# host.net
KiCad netlist of a schematic drawn in EAGLE
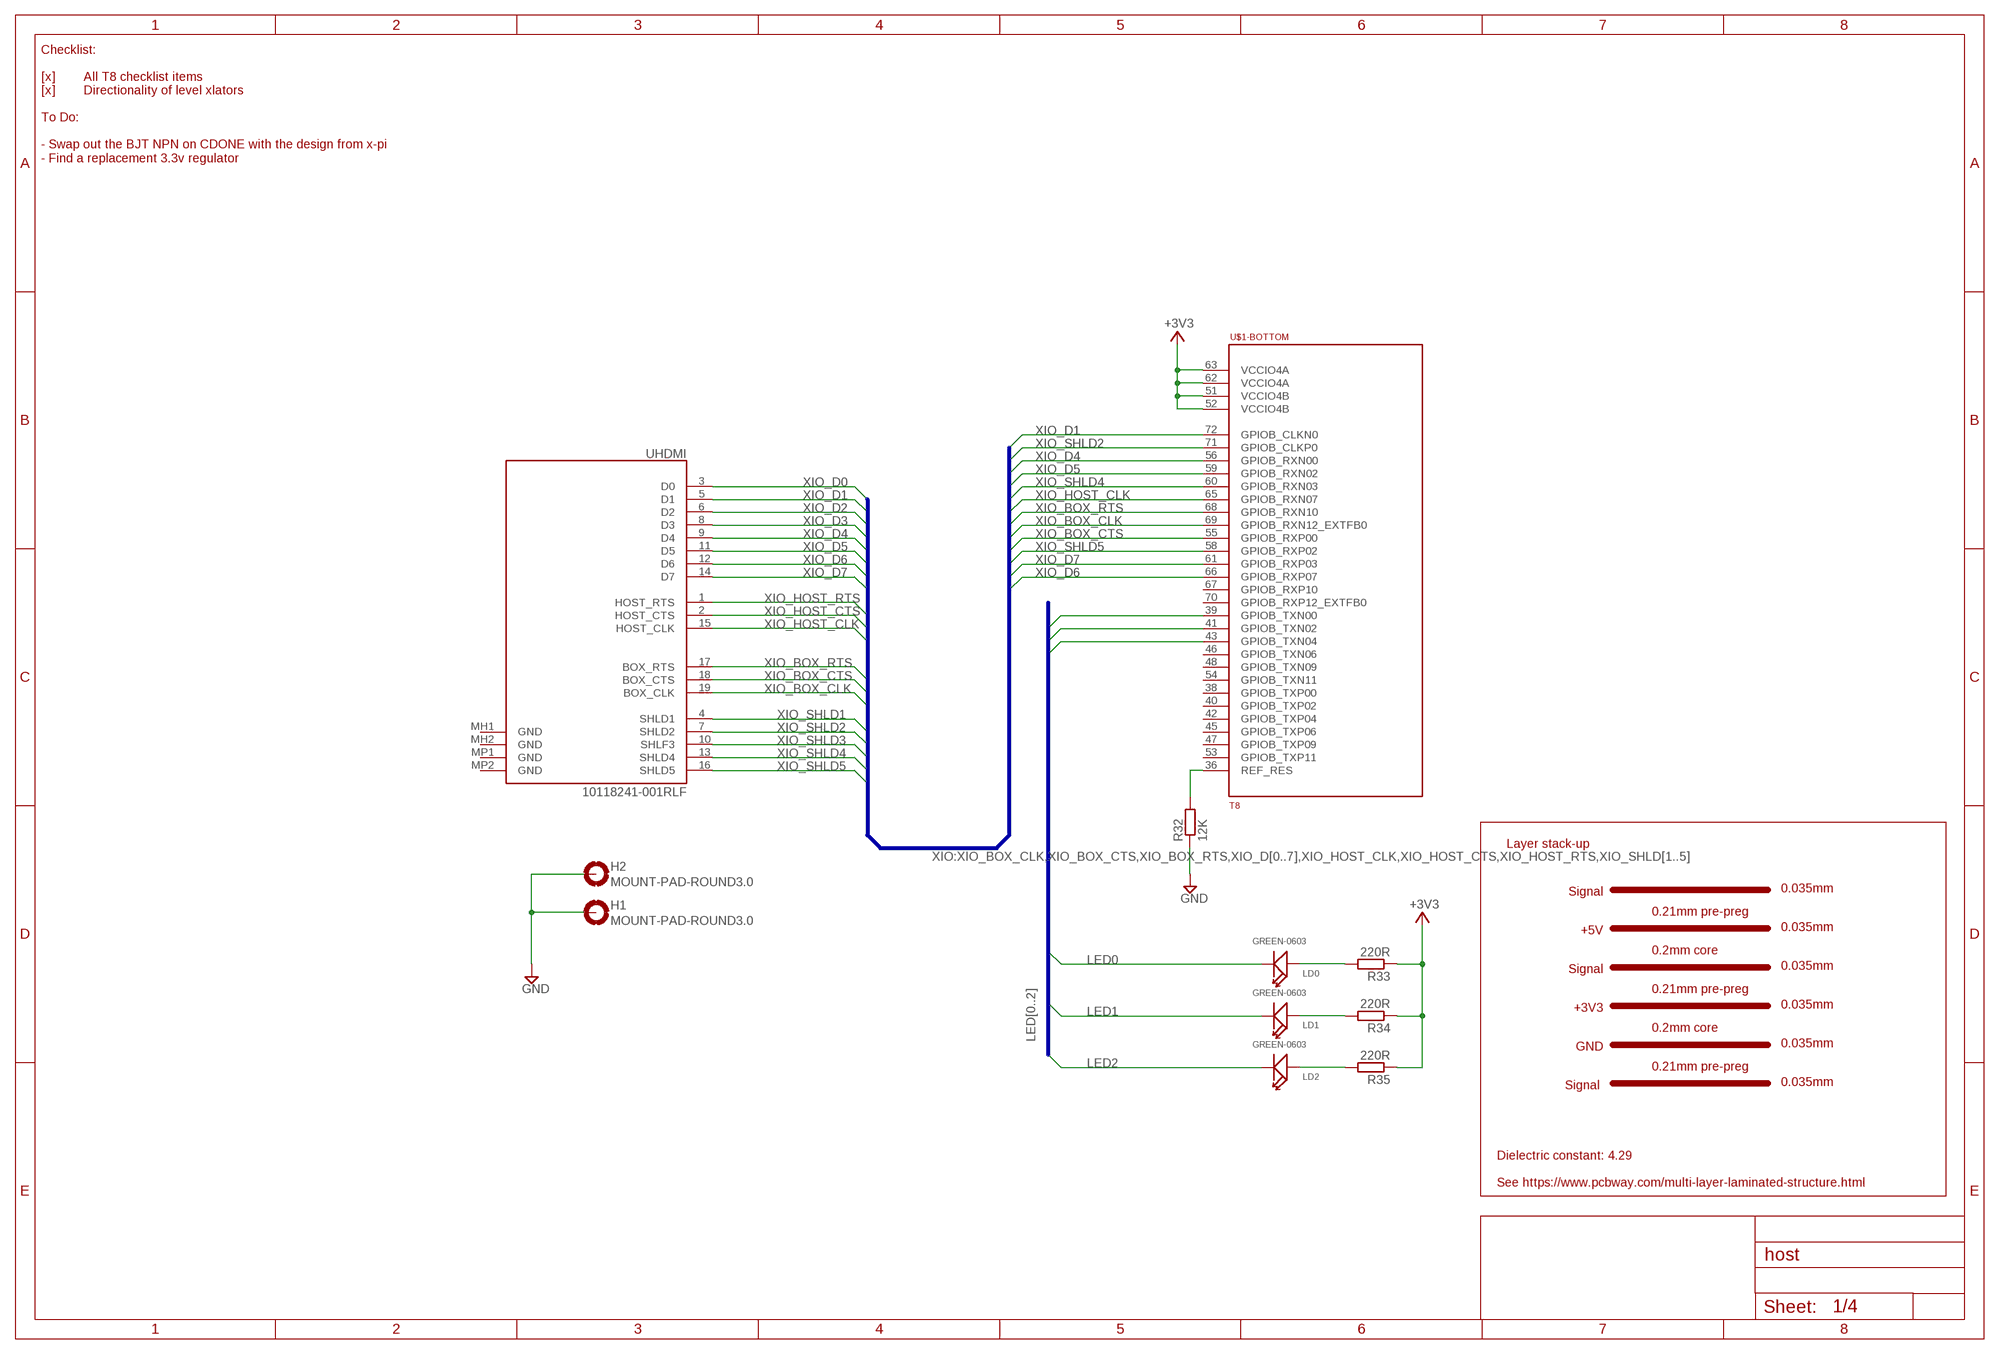
[diagram p0: schematic, sheet 1]
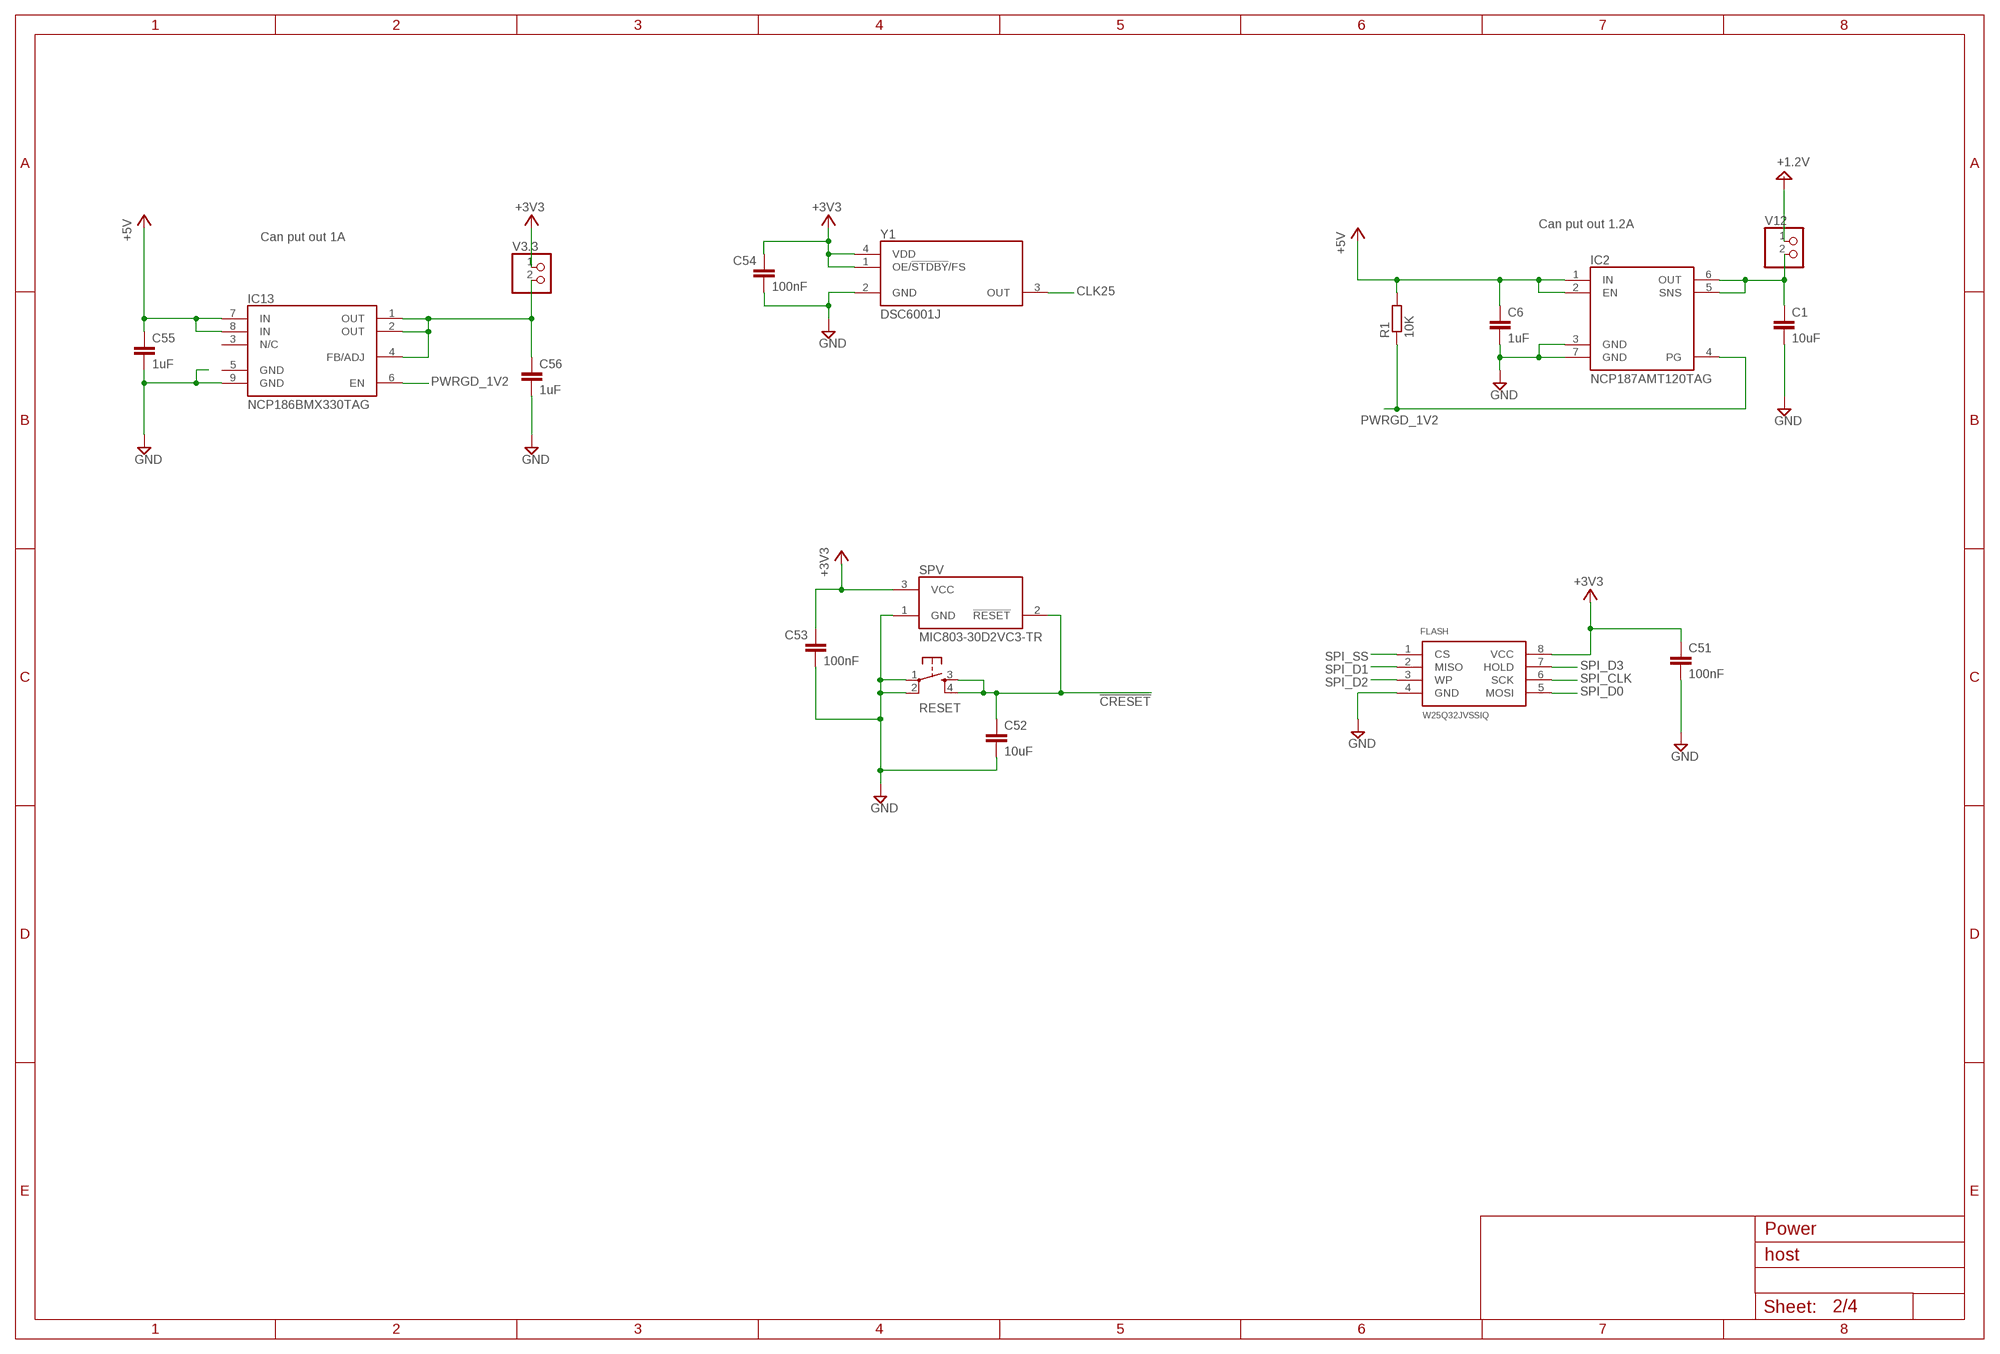
[diagram p1: schematic, sheet 2]
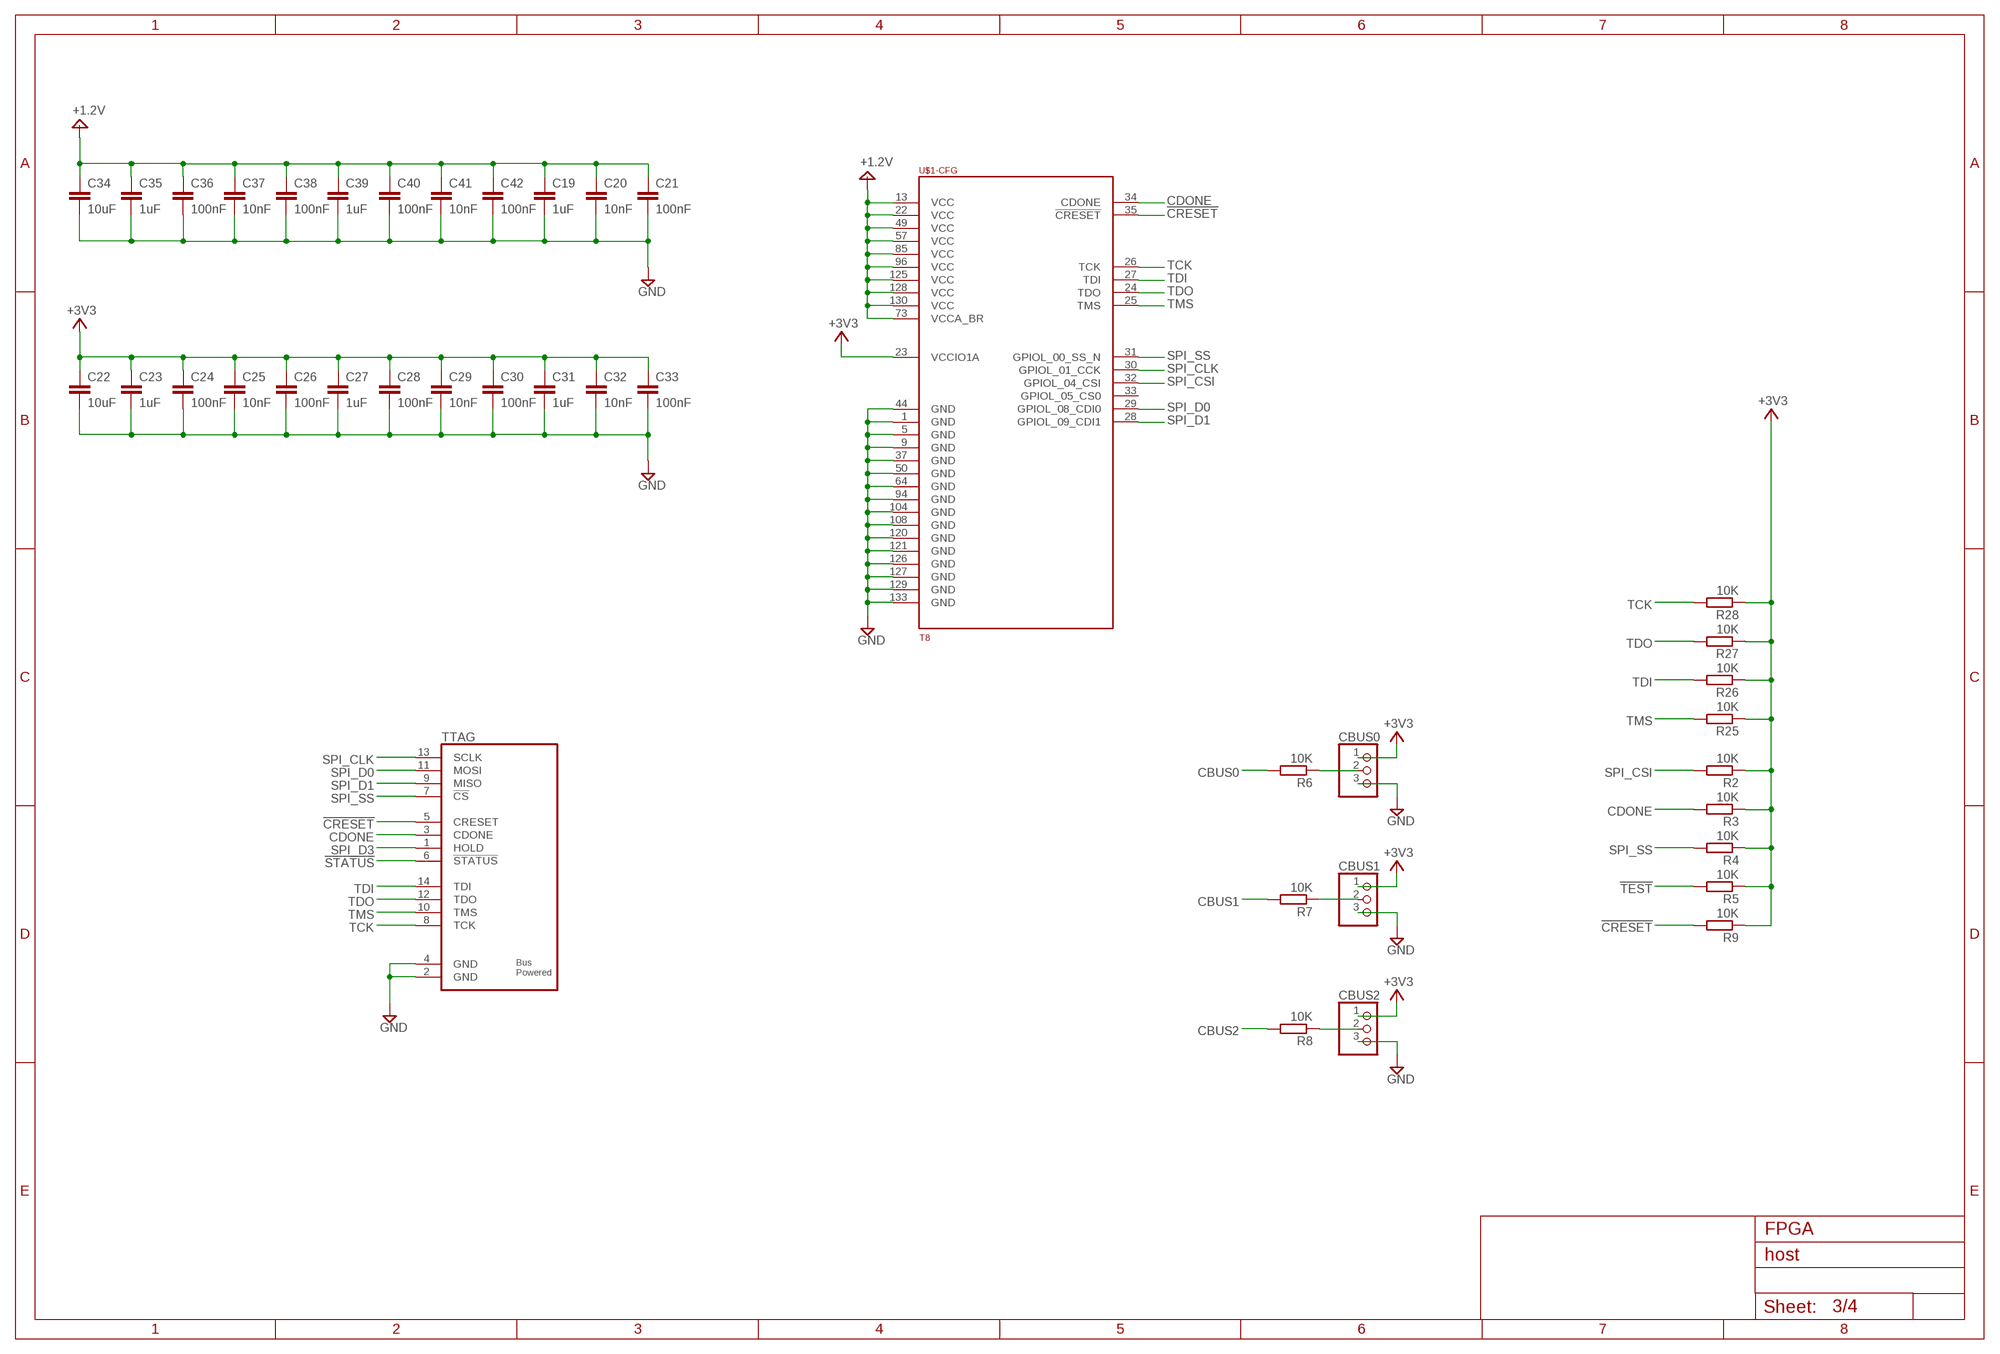
[diagram p2: schematic, sheet 3]
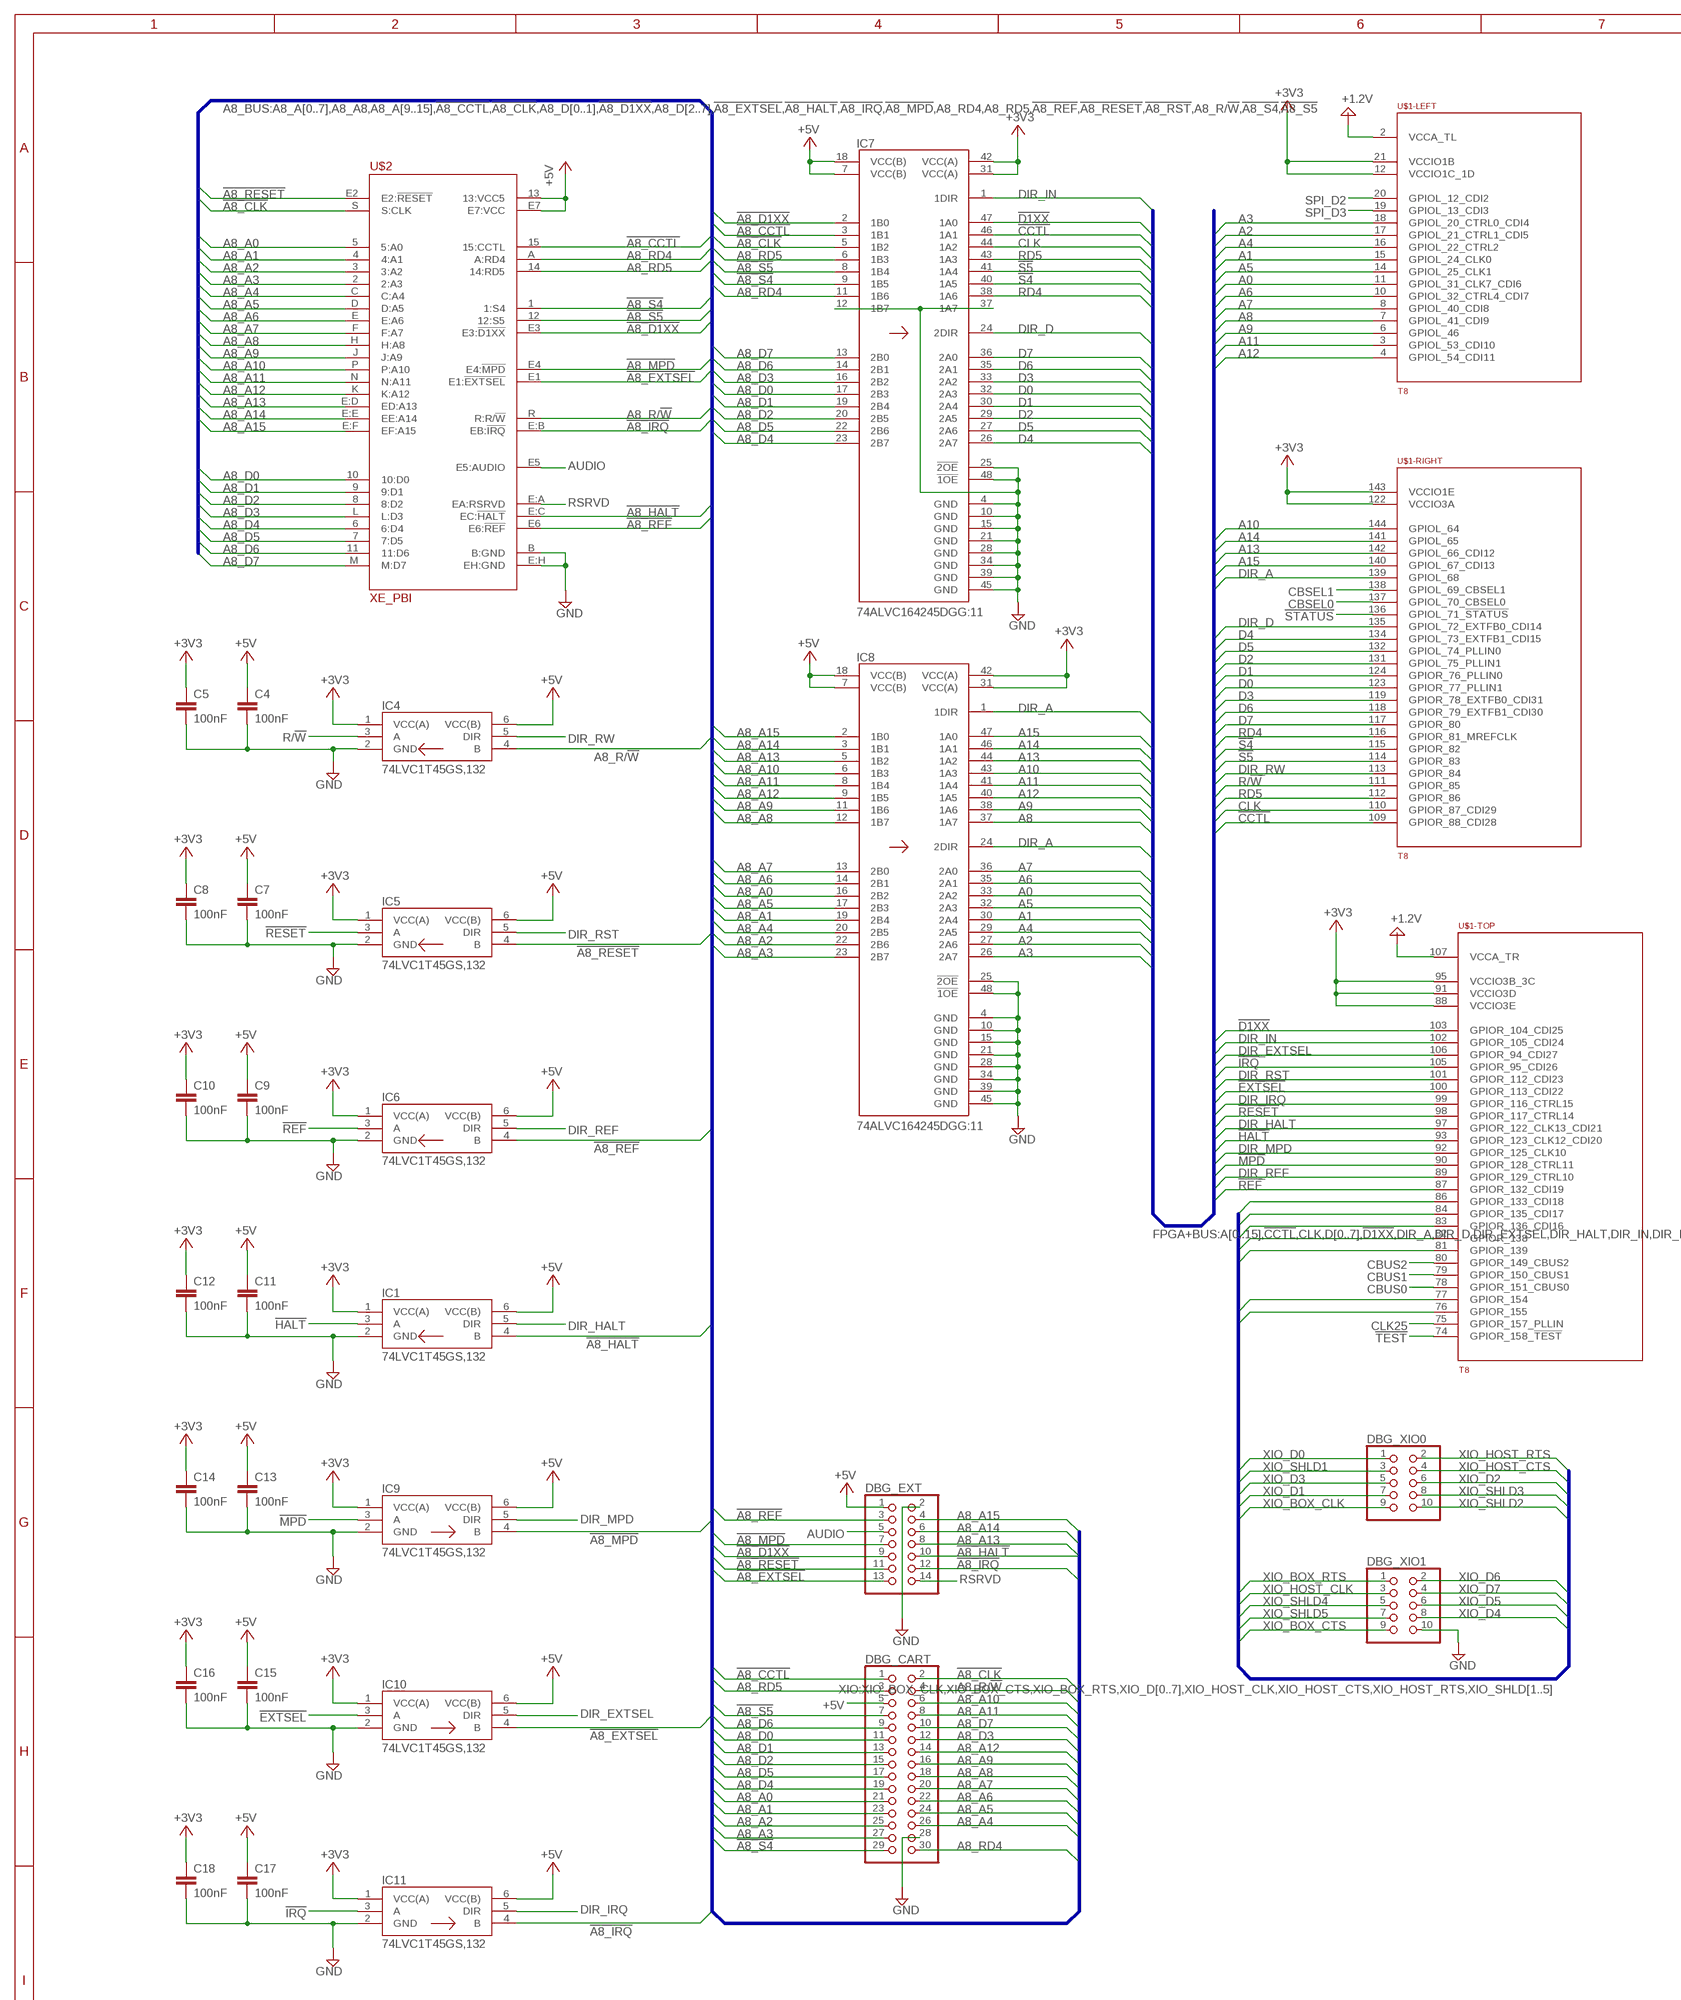
[diagram p3: schematic, sheet 4, part 1 of 2]
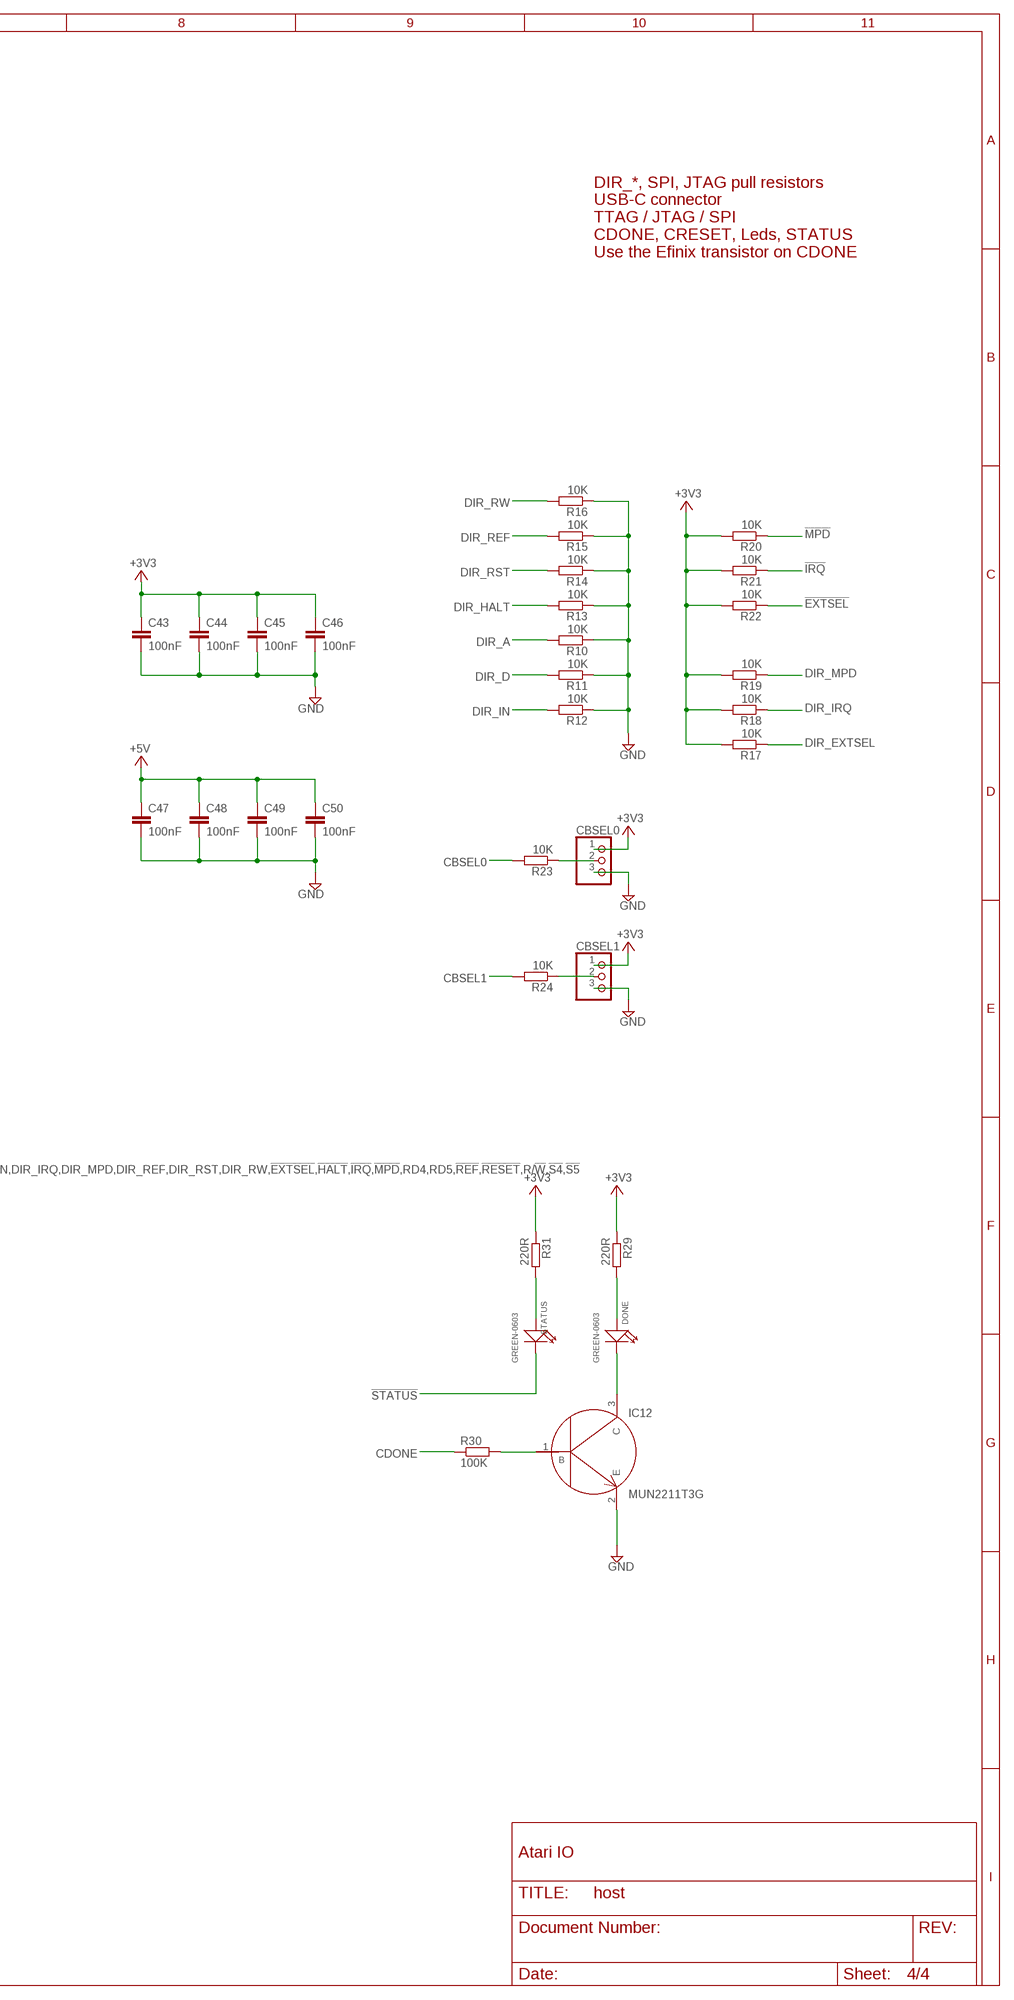
[diagram p4: schematic, sheet 4, part 2 of 2]

(export (version "E")
  (design (tool "Eeschema 10.0.6"))
  (components
    (comp (ref "H1")
      (value "MOUNT-PAD-ROUND3.0")
      (footprint "eagle-import:3,0-PAD")
      (libsource (lib "eagle-import") (part "MOUNT-PAD-ROUND3.0"))
    )
    (comp (ref "H2")
      (value "MOUNT-PAD-ROUND3.0")
      (footprint "eagle-import:3,0-PAD")
      (libsource (lib "eagle-import") (part "MOUNT-PAD-ROUND3.0"))
    )
    (comp (ref "LD0")
      (value "GREEN-0603")
      (footprint "eagle-import:LED-0603")
      (fields (field (name "MPN") "19-217-G7C-AN1P2-3T"))
      (libsource (lib "eagle-import") (part "SMD-LED-CLEAR-GREEN(0603)"))
    )
    (comp (ref "LD1")
      (value "GREEN-0603")
      (footprint "eagle-import:LED-0603")
      (fields (field (name "MPN") "19-217-G7C-AN1P2-3T"))
      (libsource (lib "eagle-import") (part "SMD-LED-CLEAR-GREEN(0603)"))
    )
    (comp (ref "LD2")
      (value "GREEN-0603")
      (footprint "eagle-import:LED-0603")
      (fields (field (name "MPN") "19-217-G7C-AN1P2-3T"))
      (libsource (lib "eagle-import") (part "SMD-LED-CLEAR-GREEN(0603)"))
    )
    (comp (ref "R32")
      (value "12K")
      (footprint "eagle-import:R0201")
      (libsource (lib "eagle-import") (part "R-EU_R0201"))
    )
    (comp (ref "R33")
      (value "220R")
      (footprint "eagle-import:R0201")
      (libsource (lib "eagle-import") (part "R-EU_R0201"))
    )
    (comp (ref "R34")
      (value "220R")
      (footprint "eagle-import:R0201")
      (libsource (lib "eagle-import") (part "R-EU_R0201"))
    )
    (comp (ref "R35")
      (value "220R")
      (footprint "eagle-import:R0201")
      (libsource (lib "eagle-import") (part "R-EU_R0201"))
    )
    (comp (ref "U$1")
      (value "T8")
      (footprint "eagle-import:TQFP144")
      (fields (field (name "USE") "T8Q144I4"))
      (libsource (lib "eagle-import") (part "T8"))
    )
    (comp (ref "UHDMI")
      (value "10118241-001RLF")
      (footprint "eagle-import:10118241001RLF")
      (fields (field (name "MOUSER_PART_NUMBER") "649-10118241-001RLF"))
      (libsource (lib "eagle-import") (part "10118241-001RLF"))
    )
    (comp (ref "C19")
      (value "1uF")
      (footprint "eagle-import:C0201")
      (libsource (lib "eagle-import") (part "C-EUC0201"))
    )
    (comp (ref "C20")
      (value "10nF")
      (footprint "eagle-import:C0201")
      (libsource (lib "eagle-import") (part "C-EUC0201"))
    )
    (comp (ref "C21")
      (value "100nF")
      (footprint "eagle-import:C0201")
      (libsource (lib "eagle-import") (part "C-EUC0201"))
    )
    (comp (ref "C22")
      (value "10uF")
      (footprint "eagle-import:C0402K")
      (libsource (lib "eagle-import") (part "C-EUC0402K"))
    )
    (comp (ref "C23")
      (value "1uF")
      (footprint "eagle-import:C0201")
      (libsource (lib "eagle-import") (part "C-EUC0201"))
    )
    (comp (ref "C24")
      (value "100nF")
      (footprint "eagle-import:C0201")
      (libsource (lib "eagle-import") (part "C-EUC0201"))
    )
    (comp (ref "C25")
      (value "10nF")
      (footprint "eagle-import:C0201")
      (libsource (lib "eagle-import") (part "C-EUC0201"))
    )
    (comp (ref "C26")
      (value "100nF")
      (footprint "eagle-import:C0201")
      (libsource (lib "eagle-import") (part "C-EUC0201"))
    )
    (comp (ref "C27")
      (value "1uF")
      (footprint "eagle-import:C0201")
      (libsource (lib "eagle-import") (part "C-EUC0201"))
    )
    (comp (ref "C28")
      (value "100nF")
      (footprint "eagle-import:C0201")
      (libsource (lib "eagle-import") (part "C-EUC0201"))
    )
    (comp (ref "C29")
      (value "10nF")
      (footprint "eagle-import:C0201")
      (libsource (lib "eagle-import") (part "C-EUC0201"))
    )
    (comp (ref "C30")
      (value "100nF")
      (footprint "eagle-import:C0201")
      (libsource (lib "eagle-import") (part "C-EUC0201"))
    )
    (comp (ref "C31")
      (value "1uF")
      (footprint "eagle-import:C0201")
      (libsource (lib "eagle-import") (part "C-EUC0201"))
    )
    (comp (ref "C32")
      (value "10nF")
      (footprint "eagle-import:C0201")
      (libsource (lib "eagle-import") (part "C-EUC0201"))
    )
    (comp (ref "C33")
      (value "100nF")
      (footprint "eagle-import:C0201")
      (libsource (lib "eagle-import") (part "C-EUC0201"))
    )
    (comp (ref "C34")
      (value "10uF")
      (footprint "eagle-import:C0402K")
      (libsource (lib "eagle-import") (part "C-EUC0402K"))
    )
    (comp (ref "C35")
      (value "1uF")
      (footprint "eagle-import:C0201")
      (libsource (lib "eagle-import") (part "C-EUC0201"))
    )
    (comp (ref "C36")
      (value "100nF")
      (footprint "eagle-import:C0201")
      (libsource (lib "eagle-import") (part "C-EUC0201"))
    )
    (comp (ref "C37")
      (value "10nF")
      (footprint "eagle-import:C0201")
      (libsource (lib "eagle-import") (part "C-EUC0201"))
    )
    (comp (ref "C38")
      (value "100nF")
      (footprint "eagle-import:C0201")
      (libsource (lib "eagle-import") (part "C-EUC0201"))
    )
    (comp (ref "C39")
      (value "1uF")
      (footprint "eagle-import:C0201")
      (libsource (lib "eagle-import") (part "C-EUC0201"))
    )
    (comp (ref "C40")
      (value "100nF")
      (footprint "eagle-import:C0201")
      (libsource (lib "eagle-import") (part "C-EUC0201"))
    )
    (comp (ref "C41")
      (value "10nF")
      (footprint "eagle-import:C0201")
      (libsource (lib "eagle-import") (part "C-EUC0201"))
    )
    (comp (ref "C42")
      (value "100nF")
      (footprint "eagle-import:C0201")
      (libsource (lib "eagle-import") (part "C-EUC0201"))
    )
    (comp (ref "CBUS0")
      (value "PINHD-1X3")
      (footprint "eagle-import:1X03")
      (libsource (lib "eagle-import") (part "PINHD-1X3"))
    )
    (comp (ref "CBUS1")
      (value "PINHD-1X3")
      (footprint "eagle-import:1X03")
      (libsource (lib "eagle-import") (part "PINHD-1X3"))
    )
    (comp (ref "CBUS2")
      (value "PINHD-1X3")
      (footprint "eagle-import:1X03")
      (libsource (lib "eagle-import") (part "PINHD-1X3"))
    )
    (comp (ref "R2")
      (value "10K")
      (footprint "eagle-import:R0201")
      (libsource (lib "eagle-import") (part "R-EU_R0201"))
    )
    (comp (ref "R3")
      (value "10K")
      (footprint "eagle-import:R0201")
      (libsource (lib "eagle-import") (part "R-EU_R0201"))
    )
    (comp (ref "R4")
      (value "10K")
      (footprint "eagle-import:R0201")
      (libsource (lib "eagle-import") (part "R-EU_R0201"))
    )
    (comp (ref "R5")
      (value "10K")
      (footprint "eagle-import:R0201")
      (libsource (lib "eagle-import") (part "R-EU_R0201"))
    )
    (comp (ref "R6")
      (value "10K")
      (footprint "eagle-import:R0201")
      (libsource (lib "eagle-import") (part "R-EU_R0201"))
    )
    (comp (ref "R7")
      (value "10K")
      (footprint "eagle-import:R0201")
      (libsource (lib "eagle-import") (part "R-EU_R0201"))
    )
    (comp (ref "R8")
      (value "10K")
      (footprint "eagle-import:R0201")
      (libsource (lib "eagle-import") (part "R-EU_R0201"))
    )
    (comp (ref "R9")
      (value "10K")
      (footprint "eagle-import:R0201")
      (libsource (lib "eagle-import") (part "R-EU_R0201"))
    )
    (comp (ref "R25")
      (value "10K")
      (footprint "eagle-import:R0201")
      (libsource (lib "eagle-import") (part "R-EU_R0201"))
    )
    (comp (ref "R26")
      (value "10K")
      (footprint "eagle-import:R0201")
      (libsource (lib "eagle-import") (part "R-EU_R0201"))
    )
    (comp (ref "R27")
      (value "10K")
      (footprint "eagle-import:R0201")
      (libsource (lib "eagle-import") (part "R-EU_R0201"))
    )
    (comp (ref "R28")
      (value "10K")
      (footprint "eagle-import:R0201")
      (libsource (lib "eagle-import") (part "R-EU_R0201"))
    )
    (comp (ref "TTAG")
      (value "TTAG_M_2.00")
      (footprint "eagle-import:2X07M")
      (libsource (lib "eagle-import") (part "TTAG_M_2.00"))
    )
    (comp (ref "C1")
      (value "10uF")
      (footprint "eagle-import:C0402K")
      (libsource (lib "eagle-import") (part "C-EUC0402K"))
    )
    (comp (ref "C6")
      (value "1uF")
      (footprint "eagle-import:C0201")
      (libsource (lib "eagle-import") (part "C-EUC0201"))
    )
    (comp (ref "C51")
      (value "100nF")
      (footprint "eagle-import:C0201")
      (libsource (lib "eagle-import") (part "C-EUC0201"))
    )
    (comp (ref "C52")
      (value "10uF")
      (footprint "eagle-import:C0402K")
      (fields (field (name "USE") "CL05A106MP5NUNC"))
      (libsource (lib "eagle-import") (part "C-EUC0402K"))
    )
    (comp (ref "C53")
      (value "100nF")
      (footprint "eagle-import:C0201")
      (libsource (lib "eagle-import") (part "C-EUC0201"))
    )
    (comp (ref "C54")
      (value "100nF")
      (footprint "eagle-import:C0201")
      (libsource (lib "eagle-import") (part "C-EUC0201"))
    )
    (comp (ref "C55")
      (value "1uF")
      (footprint "eagle-import:C0201")
      (libsource (lib "eagle-import") (part "C-EUC0201"))
    )
    (comp (ref "C56")
      (value "1uF")
      (footprint "eagle-import:C0201")
      (libsource (lib "eagle-import") (part "C-EUC0201"))
    )
    (comp (ref "FLASH")
      (value "W25Q32JVSSIQ")
      (footprint "eagle-import:SO08")
      (libsource (lib "eagle-import") (part "SPI_FLASH-X25XXSMD"))
    )
    (comp (ref "IC2")
      (value "NCP187AMT120TAG")
      (footprint "eagle-import:SON65P200X200X80-7N")
      (fields
        (field (name "ARROW_PART_NUMBER") "NCP187AMT330TAG")
        (field (name "MOUSER_PART_NUMBER") "863-NCP187AMT330TAG")
        (field (name "ARROW_PART_NUMBER_1") "NCP187AMT120TAG")
      )
      (libsource (lib "eagle-import") (part "NCP187AMT330TAG"))
    )
    (comp (ref "IC13")
      (value "NCP186BMX330TAG")
      (footprint "eagle-import:NCP186AMX330TAG")
      (fields (field (name "MOUSER_PART_NUMBER") "863-NCP186BMX330TAG"))
      (libsource (lib "eagle-import") (part "NCP186BMX330TAG"))
    )
    (comp (ref "R1")
      (value "10K")
      (footprint "eagle-import:R0201")
      (libsource (lib "eagle-import") (part "R-EU_R0201"))
    )
    (comp (ref "RESET")
      (value "TAC_SWITCHPTH")
      (footprint "eagle-import:TACTILE-PTH")
      (fields (field (name "DNF") "1") (field (name "USE") "B3F-1005"))
      (libsource (lib "eagle-import") (part "TAC_SWITCHPTH"))
    )
    (comp (ref "SPV")
      (value "MIC803-30D2VC3-TR")
      (footprint "eagle-import:SOT95P237X111-3N")
      (fields
        (field (name "ARROW_PART_NUMBER") "MIC803-30D2VM3-TR")
        (field (name "MOUSER_PART_NUMBER") "998-MIC803-30D2VM3TR")
      )
      (libsource (lib "eagle-import") (part "MIC803-30D2VM3-TR"))
    )
    (comp (ref "V3.3")
      (value "PINHD-1X2")
      (footprint "eagle-import:1X02")
      (libsource (lib "eagle-import") (part "PINHD-1X2"))
    )
    (comp (ref "V12")
      (value "PINHD-1X2")
      (footprint "eagle-import:1X02")
      (libsource (lib "eagle-import") (part "PINHD-1X2"))
    )
    (comp (ref "Y1")
      (value "DSC6001J")
      (footprint "eagle-import:DSC6001JE2B0240000")
      (fields
        (field (name "MANUFACTURER_PART_NUMBER") "DSC6001JE2B-024.0000")
        (field (name "MOUSER_PART_NUMBER") "579-6001JE2B024.0000")
      )
      (libsource (lib "eagle-import") (part "DSC6001J"))
    )
    (comp (ref "C4")
      (value "100nF")
      (footprint "eagle-import:C0201")
      (libsource (lib "eagle-import") (part "C-EUC0201"))
    )
    (comp (ref "C5")
      (value "100nF")
      (footprint "eagle-import:C0201")
      (libsource (lib "eagle-import") (part "C-EUC0201"))
    )
    (comp (ref "C7")
      (value "100nF")
      (footprint "eagle-import:C0201")
      (libsource (lib "eagle-import") (part "C-EUC0201"))
    )
    (comp (ref "C8")
      (value "100nF")
      (footprint "eagle-import:C0201")
      (libsource (lib "eagle-import") (part "C-EUC0201"))
    )
    (comp (ref "C9")
      (value "100nF")
      (footprint "eagle-import:C0201")
      (libsource (lib "eagle-import") (part "C-EUC0201"))
    )
    (comp (ref "C10")
      (value "100nF")
      (footprint "eagle-import:C0201")
      (libsource (lib "eagle-import") (part "C-EUC0201"))
    )
    (comp (ref "C11")
      (value "100nF")
      (footprint "eagle-import:C0201")
      (libsource (lib "eagle-import") (part "C-EUC0201"))
    )
    (comp (ref "C12")
      (value "100nF")
      (footprint "eagle-import:C0201")
      (libsource (lib "eagle-import") (part "C-EUC0201"))
    )
    (comp (ref "C13")
      (value "100nF")
      (footprint "eagle-import:C0201")
      (libsource (lib "eagle-import") (part "C-EUC0201"))
    )
    (comp (ref "C14")
      (value "100nF")
      (footprint "eagle-import:C0201")
      (libsource (lib "eagle-import") (part "C-EUC0201"))
    )
    (comp (ref "C15")
      (value "100nF")
      (footprint "eagle-import:C0201")
      (libsource (lib "eagle-import") (part "C-EUC0201"))
    )
    (comp (ref "C16")
      (value "100nF")
      (footprint "eagle-import:C0201")
      (libsource (lib "eagle-import") (part "C-EUC0201"))
    )
    (comp (ref "C17")
      (value "100nF")
      (footprint "eagle-import:C0201")
      (libsource (lib "eagle-import") (part "C-EUC0201"))
    )
    (comp (ref "C18")
      (value "100nF")
      (footprint "eagle-import:C0201")
      (libsource (lib "eagle-import") (part "C-EUC0201"))
    )
    (comp (ref "C43")
      (value "100nF")
      (footprint "eagle-import:C0201")
      (libsource (lib "eagle-import") (part "C-EUC0201"))
    )
    (comp (ref "C44")
      (value "100nF")
      (footprint "eagle-import:C0201")
      (libsource (lib "eagle-import") (part "C-EUC0201"))
    )
    (comp (ref "C45")
      (value "100nF")
      (footprint "eagle-import:C0201")
      (libsource (lib "eagle-import") (part "C-EUC0201"))
    )
    (comp (ref "C46")
      (value "100nF")
      (footprint "eagle-import:C0201")
      (libsource (lib "eagle-import") (part "C-EUC0201"))
    )
    (comp (ref "C47")
      (value "100nF")
      (footprint "eagle-import:C0201")
      (libsource (lib "eagle-import") (part "C-EUC0201"))
    )
    (comp (ref "C48")
      (value "100nF")
      (footprint "eagle-import:C0201")
      (libsource (lib "eagle-import") (part "C-EUC0201"))
    )
    (comp (ref "C49")
      (value "100nF")
      (footprint "eagle-import:C0201")
      (libsource (lib "eagle-import") (part "C-EUC0201"))
    )
    (comp (ref "C50")
      (value "100nF")
      (footprint "eagle-import:C0201")
      (libsource (lib "eagle-import") (part "C-EUC0201"))
    )
    (comp (ref "CBSEL0")
      (value "PINHD-1X3")
      (footprint "eagle-import:1X03")
      (libsource (lib "eagle-import") (part "PINHD-1X3"))
    )
    (comp (ref "CBSEL1")
      (value "PINHD-1X3")
      (footprint "eagle-import:1X03")
      (libsource (lib "eagle-import") (part "PINHD-1X3"))
    )
    (comp (ref "DBG_CART")
      (value "PINHD-2X15_2.54")
      (footprint "eagle-import:2X15")
      (libsource (lib "eagle-import") (part "PINHD-2X15_2.54"))
    )
    (comp (ref "DBG_EXT")
      (value "PINHD-2X07_2.54")
      (footprint "eagle-import:2X07")
      (libsource (lib "eagle-import") (part "PINHD-2X07_2.54"))
    )
    (comp (ref "DBG_XIO0")
      (value "PINHD-2X5")
      (footprint "eagle-import:2X05")
      (libsource (lib "eagle-import") (part "PINHD-2X5"))
    )
    (comp (ref "DBG_XIO1")
      (value "PINHD-2X5")
      (footprint "eagle-import:2X05")
      (libsource (lib "eagle-import") (part "PINHD-2X5"))
    )
    (comp (ref "DONE")
      (value "GREEN-0603")
      (footprint "eagle-import:LED-0603")
      (fields (field (name "MPN") "19-217-G7C-AN1P2-3T"))
      (libsource (lib "eagle-import") (part "SMD-LED-CLEAR-GREEN(0603)"))
    )
    (comp (ref "IC1")
      (value "74LVC1T45GS,132")
      (footprint "eagle-import:74LVC1G3157GS132")
      (fields (field (name "MOUSER_PART_NUMBER") "771-74LVC1T45GS132"))
      (libsource (lib "eagle-import") (part "74LVC1T45GS,132"))
    )
    (comp (ref "IC4")
      (value "74LVC1T45GS,132")
      (footprint "eagle-import:74LVC1G3157GS132")
      (fields (field (name "MOUSER_PART_NUMBER") "771-74LVC1T45GS132"))
      (libsource (lib "eagle-import") (part "74LVC1T45GS,132"))
    )
    (comp (ref "IC5")
      (value "74LVC1T45GS,132")
      (footprint "eagle-import:74LVC1G3157GS132")
      (fields (field (name "MOUSER_PART_NUMBER") "771-74LVC1T45GS132"))
      (libsource (lib "eagle-import") (part "74LVC1T45GS,132"))
    )
    (comp (ref "IC6")
      (value "74LVC1T45GS,132")
      (footprint "eagle-import:74LVC1G3157GS132")
      (fields (field (name "MOUSER_PART_NUMBER") "771-74LVC1T45GS132"))
      (libsource (lib "eagle-import") (part "74LVC1T45GS,132"))
    )
    (comp (ref "IC7")
      (value "74ALVC164245DGG:11")
      (footprint "eagle-import:SOP50P810X120-48N")
      (fields (field (name "MOUSER_PART_NUMBER") "771-74ALVC164245"))
      (libsource (lib "eagle-import") (part "74ALVC164245DGG_11"))
    )
    (comp (ref "IC8")
      (value "74ALVC164245DGG:11")
      (footprint "eagle-import:SOP50P810X120-48N")
      (fields (field (name "MOUSER_PART_NUMBER") "771-74ALVC164245"))
      (libsource (lib "eagle-import") (part "74ALVC164245DGG_11"))
    )
    (comp (ref "IC9")
      (value "74LVC1T45GS,132")
      (footprint "eagle-import:74LVC1G3157GS132")
      (fields (field (name "MOUSER_PART_NUMBER") "771-74LVC1T45GS132"))
      (libsource (lib "eagle-import") (part "74LVC1T45GS,132"))
    )
    (comp (ref "IC10")
      (value "74LVC1T45GS,132")
      (footprint "eagle-import:74LVC1G3157GS132")
      (fields (field (name "MOUSER_PART_NUMBER") "771-74LVC1T45GS132"))
      (libsource (lib "eagle-import") (part "74LVC1T45GS,132"))
    )
    (comp (ref "IC11")
      (value "74LVC1T45GS,132")
      (footprint "eagle-import:74LVC1G3157GS132")
      (fields (field (name "MOUSER_PART_NUMBER") "771-74LVC1T45GS132"))
      (libsource (lib "eagle-import") (part "74LVC1T45GS,132"))
    )
    (comp (ref "IC12")
      (value "MUN2211T3G")
      (footprint "eagle-import:SOTFL50P160X78-3N")
      (fields
        (field (name "ARROW_PART_NUMBER") "MMBT3904T")
        (field (name "MOUSER_PART_NUMBER") "512-MMBT3904T")
      )
      (libsource (lib "eagle-import") (part "MMBT3904T"))
    )
    (comp (ref "R10")
      (value "10K")
      (footprint "eagle-import:R0201")
      (libsource (lib "eagle-import") (part "R-EU_R0201"))
    )
    (comp (ref "R11")
      (value "10K")
      (footprint "eagle-import:R0201")
      (libsource (lib "eagle-import") (part "R-EU_R0201"))
    )
    (comp (ref "R12")
      (value "10K")
      (footprint "eagle-import:R0201")
      (libsource (lib "eagle-import") (part "R-EU_R0201"))
    )
    (comp (ref "R13")
      (value "10K")
      (footprint "eagle-import:R0201")
      (libsource (lib "eagle-import") (part "R-EU_R0201"))
    )
    (comp (ref "R14")
      (value "10K")
      (footprint "eagle-import:R0201")
      (libsource (lib "eagle-import") (part "R-EU_R0201"))
    )
    (comp (ref "R15")
      (value "10K")
      (footprint "eagle-import:R0201")
      (libsource (lib "eagle-import") (part "R-EU_R0201"))
    )
    (comp (ref "R16")
      (value "10K")
      (footprint "eagle-import:R0201")
      (libsource (lib "eagle-import") (part "R-EU_R0201"))
    )
    (comp (ref "R17")
      (value "10K")
      (footprint "eagle-import:R0201")
      (libsource (lib "eagle-import") (part "R-EU_R0201"))
    )
    (comp (ref "R18")
      (value "10K")
      (footprint "eagle-import:R0201")
      (libsource (lib "eagle-import") (part "R-EU_R0201"))
    )
    (comp (ref "R19")
      (value "10K")
      (footprint "eagle-import:R0201")
      (libsource (lib "eagle-import") (part "R-EU_R0201"))
    )
    (comp (ref "R20")
      (value "10K")
      (footprint "eagle-import:R0201")
      (libsource (lib "eagle-import") (part "R-EU_R0201"))
    )
    (comp (ref "R21")
      (value "10K")
      (footprint "eagle-import:R0201")
      (libsource (lib "eagle-import") (part "R-EU_R0201"))
    )
    (comp (ref "R22")
      (value "10K")
      (footprint "eagle-import:R0201")
      (libsource (lib "eagle-import") (part "R-EU_R0201"))
    )
    (comp (ref "R23")
      (value "10K")
      (footprint "eagle-import:R0201")
      (libsource (lib "eagle-import") (part "R-EU_R0201"))
    )
    (comp (ref "R24")
      (value "10K")
      (footprint "eagle-import:R0201")
      (libsource (lib "eagle-import") (part "R-EU_R0201"))
    )
    (comp (ref "R29")
      (value "220R")
      (footprint "eagle-import:R0201")
      (libsource (lib "eagle-import") (part "R-EU_R0201"))
    )
    (comp (ref "R30")
      (value "100K")
      (footprint "eagle-import:R0201")
      (libsource (lib "eagle-import") (part "R-EU_R0201"))
    )
    (comp (ref "R31")
      (value "220R")
      (footprint "eagle-import:R0201")
      (libsource (lib "eagle-import") (part "R-EU_R0201"))
    )
    (comp (ref "STATUS")
      (value "GREEN-0603")
      (footprint "eagle-import:LED-0603")
      (fields (field (name "MPN") "19-217-G7C-AN1P2-3T"))
      (libsource (lib "eagle-import") (part "SMD-LED-CLEAR-GREEN(0603)"))
    )
    (comp (ref "U$2")
      (value "XE_PBI")
      (footprint "eagle-import:XE_PBI")
      (libsource (lib "eagle-import") (part "XE_PBI"))
    )
  )
  (nets
    (net (code "4") (name "+1.2V") (class "Default")
      (node (ref "C19") (pin "1") (pinfunction "1_1") (pintype "passive"))
      (node (ref "C20") (pin "1") (pinfunction "1_1") (pintype "passive"))
      (node (ref "C21") (pin "1") (pinfunction "1_1") (pintype "passive"))
      (node (ref "C34") (pin "1") (pinfunction "1_1") (pintype "passive"))
      (node (ref "C35") (pin "1") (pinfunction "1_1") (pintype "passive"))
      (node (ref "C36") (pin "1") (pinfunction "1_1") (pintype "passive"))
      (node (ref "C37") (pin "1") (pinfunction "1_1") (pintype "passive"))
      (node (ref "C38") (pin "1") (pinfunction "1_1") (pintype "passive"))
      (node (ref "C39") (pin "1") (pinfunction "1_1") (pintype "passive"))
      (node (ref "C40") (pin "1") (pinfunction "1_1") (pintype "passive"))
      (node (ref "C41") (pin "1") (pinfunction "1_1") (pintype "passive"))
      (node (ref "C42") (pin "1") (pinfunction "1_1") (pintype "passive"))
      (node (ref "U$1") (pin "107") (pinfunction "VCCA_TR_107") (pintype "bidirectional"))
      (node (ref "U$1") (pin "125") (pinfunction "VCC_125") (pintype "bidirectional"))
      (node (ref "U$1") (pin "128") (pinfunction "VCC_128") (pintype "bidirectional"))
      (node (ref "U$1") (pin "13") (pinfunction "VCC_13") (pintype "bidirectional"))
      (node (ref "U$1") (pin "130") (pinfunction "VCC_130") (pintype "bidirectional"))
      (node (ref "U$1") (pin "2") (pinfunction "VCCA_TL_2") (pintype "bidirectional"))
      (node (ref "U$1") (pin "22") (pinfunction "VCC_22") (pintype "bidirectional"))
      (node (ref "U$1") (pin "49") (pinfunction "VCC_49") (pintype "bidirectional"))
      (node (ref "U$1") (pin "57") (pinfunction "VCC_57") (pintype "bidirectional"))
      (node (ref "U$1") (pin "73") (pinfunction "VCCA_BR_73") (pintype "bidirectional"))
      (node (ref "U$1") (pin "85") (pinfunction "VCC_85") (pintype "bidirectional"))
      (node (ref "U$1") (pin "96") (pinfunction "VCC_96") (pintype "bidirectional"))
      (node (ref "V12") (pin "1") (pinfunction "1_1") (pintype "passive"))
    )
    (net (code "5") (name "+3V3") (class "Default")
      (node (ref "C10") (pin "1") (pinfunction "1_1") (pintype "passive"))
      (node (ref "C12") (pin "1") (pinfunction "1_1") (pintype "passive"))
      (node (ref "C14") (pin "1") (pinfunction "1_1") (pintype "passive"))
      (node (ref "C16") (pin "1") (pinfunction "1_1") (pintype "passive"))
      (node (ref "C18") (pin "1") (pinfunction "1_1") (pintype "passive"))
      (node (ref "C22") (pin "1") (pinfunction "1_1") (pintype "passive"))
      (node (ref "C23") (pin "1") (pinfunction "1_1") (pintype "passive"))
      (node (ref "C24") (pin "1") (pinfunction "1_1") (pintype "passive"))
      (node (ref "C25") (pin "1") (pinfunction "1_1") (pintype "passive"))
      (node (ref "C26") (pin "1") (pinfunction "1_1") (pintype "passive"))
      (node (ref "C27") (pin "1") (pinfunction "1_1") (pintype "passive"))
      (node (ref "C28") (pin "1") (pinfunction "1_1") (pintype "passive"))
      (node (ref "C29") (pin "1") (pinfunction "1_1") (pintype "passive"))
      (node (ref "C30") (pin "1") (pinfunction "1_1") (pintype "passive"))
      (node (ref "C31") (pin "1") (pinfunction "1_1") (pintype "passive"))
      (node (ref "C32") (pin "1") (pinfunction "1_1") (pintype "passive"))
      (node (ref "C33") (pin "1") (pinfunction "1_1") (pintype "passive"))
      (node (ref "C43") (pin "1") (pinfunction "1_1") (pintype "passive"))
      (node (ref "C44") (pin "1") (pinfunction "1_1") (pintype "passive"))
      (node (ref "C45") (pin "1") (pinfunction "1_1") (pintype "passive"))
      (node (ref "C46") (pin "1") (pinfunction "1_1") (pintype "passive"))
      (node (ref "C5") (pin "1") (pinfunction "1_1") (pintype "passive"))
      (node (ref "C51") (pin "1") (pinfunction "1_1") (pintype "passive"))
      (node (ref "C53") (pin "1") (pinfunction "1_1") (pintype "passive"))
      (node (ref "C54") (pin "1") (pinfunction "1_1") (pintype "passive"))
      (node (ref "C8") (pin "1") (pinfunction "1_1") (pintype "passive"))
      (node (ref "CBSEL0") (pin "1") (pinfunction "1_1") (pintype "passive"))
      (node (ref "CBSEL1") (pin "1") (pinfunction "1_1") (pintype "passive"))
      (node (ref "CBUS0") (pin "1") (pinfunction "1_1") (pintype "passive"))
      (node (ref "CBUS1") (pin "1") (pinfunction "1_1") (pintype "passive"))
      (node (ref "CBUS2") (pin "1") (pinfunction "1_1") (pintype "passive"))
      (node (ref "FLASH") (pin "8") (pinfunction "VCC_8") (pintype "bidirectional"))
      (node (ref "IC1") (pin "1") (pinfunction "VCC(A)_1") (pintype "bidirectional"))
      (node (ref "IC10") (pin "1") (pinfunction "VCC(A)_1") (pintype "bidirectional"))
      (node (ref "IC11") (pin "1") (pinfunction "VCC(A)_1") (pintype "bidirectional"))
      (node (ref "IC4") (pin "1") (pinfunction "VCC(A)_1") (pintype "bidirectional"))
      (node (ref "IC5") (pin "1") (pinfunction "VCC(A)_1") (pintype "bidirectional"))
      (node (ref "IC6") (pin "1") (pinfunction "VCC(A)_1") (pintype "bidirectional"))
      (node (ref "IC7") (pin "31") (pinfunction "VCC(A)_31") (pintype "bidirectional"))
      (node (ref "IC7") (pin "42") (pinfunction "VCC(A)_42") (pintype "bidirectional"))
      (node (ref "IC8") (pin "31") (pinfunction "VCC(A)_31") (pintype "bidirectional"))
      (node (ref "IC8") (pin "42") (pinfunction "VCC(A)_42") (pintype "bidirectional"))
      (node (ref "IC9") (pin "1") (pinfunction "VCC(A)_1") (pintype "bidirectional"))
      (node (ref "R17") (pin "2") (pinfunction "2_2") (pintype "passive"))
      (node (ref "R18") (pin "2") (pinfunction "2_2") (pintype "passive"))
      (node (ref "R19") (pin "2") (pinfunction "2_2") (pintype "passive"))
      (node (ref "R2") (pin "1") (pinfunction "1_1") (pintype "passive"))
      (node (ref "R20") (pin "2") (pinfunction "2_2") (pintype "passive"))
      (node (ref "R21") (pin "2") (pinfunction "2_2") (pintype "passive"))
      (node (ref "R22") (pin "2") (pinfunction "2_2") (pintype "passive"))
      (node (ref "R25") (pin "1") (pinfunction "1_1") (pintype "passive"))
      (node (ref "R26") (pin "1") (pinfunction "1_1") (pintype "passive"))
      (node (ref "R27") (pin "1") (pinfunction "1_1") (pintype "passive"))
      (node (ref "R28") (pin "1") (pinfunction "1_1") (pintype "passive"))
      (node (ref "R29") (pin "1") (pinfunction "1_1") (pintype "passive"))
      (node (ref "R3") (pin "1") (pinfunction "1_1") (pintype "passive"))
      (node (ref "R31") (pin "1") (pinfunction "1_1") (pintype "passive"))
      (node (ref "R33") (pin "1") (pinfunction "1_1") (pintype "passive"))
      (node (ref "R34") (pin "1") (pinfunction "1_1") (pintype "passive"))
      (node (ref "R35") (pin "1") (pinfunction "1_1") (pintype "passive"))
      (node (ref "R4") (pin "1") (pinfunction "1_1") (pintype "passive"))
      (node (ref "R5") (pin "1") (pinfunction "1_1") (pintype "passive"))
      (node (ref "R9") (pin "1") (pinfunction "1_1") (pintype "passive"))
      (node (ref "SPV") (pin "3") (pinfunction "VCC_3") (pintype "bidirectional"))
      (node (ref "U$1") (pin "12") (pinfunction "VCCIO1C_1D_12") (pintype "bidirectional"))
      (node (ref "U$1") (pin "122") (pinfunction "VCCIO3A_122") (pintype "bidirectional"))
      (node (ref "U$1") (pin "143") (pinfunction "VCCIO1E_143") (pintype "bidirectional"))
      (node (ref "U$1") (pin "21") (pinfunction "VCCIO1B_21") (pintype "bidirectional"))
      (node (ref "U$1") (pin "23") (pinfunction "VCCIO1A_23") (pintype "bidirectional"))
      (node (ref "U$1") (pin "51") (pinfunction "VCCIO4B_51") (pintype "bidirectional"))
      (node (ref "U$1") (pin "52") (pinfunction "VCCIO4B_52") (pintype "bidirectional"))
      (node (ref "U$1") (pin "62") (pinfunction "VCCIO4A_62") (pintype "bidirectional"))
      (node (ref "U$1") (pin "63") (pinfunction "VCCIO4A_63") (pintype "bidirectional"))
      (node (ref "U$1") (pin "88") (pinfunction "VCCIO3E_88") (pintype "bidirectional"))
      (node (ref "U$1") (pin "91") (pinfunction "VCCIO3D_91") (pintype "bidirectional"))
      (node (ref "U$1") (pin "95") (pinfunction "VCCIO3B_3C_95") (pintype "bidirectional"))
      (node (ref "V3.3") (pin "1") (pinfunction "1_1") (pintype "passive"))
      (node (ref "Y1") (pin "1") (pinfunction "OE/~{STDBY}/FS_1") (pintype "bidirectional"))
      (node (ref "Y1") (pin "4") (pinfunction "VDD_4") (pintype "bidirectional"))
    )
    (net (code "6") (name "+5V") (class "Default")
      (node (ref "C11") (pin "1") (pinfunction "1_1") (pintype "passive"))
      (node (ref "C13") (pin "1") (pinfunction "1_1") (pintype "passive"))
      (node (ref "C15") (pin "1") (pinfunction "1_1") (pintype "passive"))
      (node (ref "C17") (pin "1") (pinfunction "1_1") (pintype "passive"))
      (node (ref "C4") (pin "1") (pinfunction "1_1") (pintype "passive"))
      (node (ref "C47") (pin "1") (pinfunction "1_1") (pintype "passive"))
      (node (ref "C48") (pin "1") (pinfunction "1_1") (pintype "passive"))
      (node (ref "C49") (pin "1") (pinfunction "1_1") (pintype "passive"))
      (node (ref "C50") (pin "1") (pinfunction "1_1") (pintype "passive"))
      (node (ref "C55") (pin "1") (pinfunction "1_1") (pintype "passive"))
      (node (ref "C6") (pin "1") (pinfunction "1_1") (pintype "passive"))
      (node (ref "C7") (pin "1") (pinfunction "1_1") (pintype "passive"))
      (node (ref "C9") (pin "1") (pinfunction "1_1") (pintype "passive"))
      (node (ref "DBG_CART") (pin "5") (pinfunction "5_5") (pintype "passive"))
      (node (ref "DBG_EXT") (pin "1") (pinfunction "1_1") (pintype "passive"))
      (node (ref "IC1") (pin "6") (pinfunction "VCC(B)_6") (pintype "bidirectional"))
      (node (ref "IC10") (pin "6") (pinfunction "VCC(B)_6") (pintype "bidirectional"))
      (node (ref "IC11") (pin "6") (pinfunction "VCC(B)_6") (pintype "bidirectional"))
      (node (ref "IC13") (pin "7") (pinfunction "IN_7") (pintype "bidirectional"))
      (node (ref "IC13") (pin "8") (pinfunction "IN_8") (pintype "bidirectional"))
      (node (ref "IC2") (pin "1") (pinfunction "IN_1") (pintype "bidirectional"))
      (node (ref "IC2") (pin "2") (pinfunction "EN_2") (pintype "bidirectional"))
      (node (ref "IC4") (pin "6") (pinfunction "VCC(B)_6") (pintype "bidirectional"))
      (node (ref "IC5") (pin "6") (pinfunction "VCC(B)_6") (pintype "bidirectional"))
      (node (ref "IC6") (pin "6") (pinfunction "VCC(B)_6") (pintype "bidirectional"))
      (node (ref "IC7") (pin "18") (pinfunction "VCC(B)_18") (pintype "bidirectional"))
      (node (ref "IC7") (pin "7") (pinfunction "VCC(B)_7") (pintype "bidirectional"))
      (node (ref "IC8") (pin "18") (pinfunction "VCC(B)_18") (pintype "bidirectional"))
      (node (ref "IC8") (pin "7") (pinfunction "VCC(B)_7") (pintype "bidirectional"))
      (node (ref "IC9") (pin "6") (pinfunction "VCC(B)_6") (pintype "bidirectional"))
      (node (ref "R1") (pin "2") (pinfunction "2_2") (pintype "passive"))
      (node (ref "U$2") (pin "13") (pinfunction "13:VCC5_13") (pintype "bidirectional"))
      (node (ref "U$2") (pin "E7") (pinfunction "E7:VCC_E7") (pintype "bidirectional"))
    )
    (net (code "12") (name "A0") (class "Default")
      (node (ref "IC8") (pin "33") (pinfunction "2A2_33") (pintype "bidirectional"))
      (node (ref "U$1") (pin "11") (pinfunction "GPIOL_31_CLK7_CDI6_11") (pintype "bidirectional"))
    )
    (net (code "13") (name "A1") (class "Default")
      (node (ref "IC8") (pin "30") (pinfunction "2A4_30") (pintype "bidirectional"))
      (node (ref "U$1") (pin "15") (pinfunction "GPIOL_24_CLK0_15") (pintype "bidirectional"))
    )
    (net (code "14") (name "A2") (class "Default")
      (node (ref "IC8") (pin "27") (pinfunction "2A6_27") (pintype "bidirectional"))
      (node (ref "U$1") (pin "17") (pinfunction "GPIOL_21_CTRL1_CDI5_17") (pintype "bidirectional"))
    )
    (net (code "15") (name "A3") (class "Default")
      (node (ref "IC8") (pin "26") (pinfunction "2A7_26") (pintype "bidirectional"))
      (node (ref "U$1") (pin "18") (pinfunction "GPIOL_20_CTRL0_CDI4_18") (pintype "bidirectional"))
    )
    (net (code "16") (name "A4") (class "Default")
      (node (ref "IC8") (pin "29") (pinfunction "2A5_29") (pintype "bidirectional"))
      (node (ref "U$1") (pin "16") (pinfunction "GPIOL_22_CTRL2_16") (pintype "bidirectional"))
    )
    (net (code "17") (name "A5") (class "Default")
      (node (ref "IC8") (pin "32") (pinfunction "2A3_32") (pintype "bidirectional"))
      (node (ref "U$1") (pin "14") (pinfunction "GPIOL_25_CLK1_14") (pintype "bidirectional"))
    )
    (net (code "18") (name "A6") (class "Default")
      (node (ref "IC8") (pin "35") (pinfunction "2A1_35") (pintype "bidirectional"))
      (node (ref "U$1") (pin "10") (pinfunction "GPIOL_32_CTRL4_CDI7_10") (pintype "bidirectional"))
    )
    (net (code "19") (name "A7") (class "Default")
      (node (ref "IC8") (pin "36") (pinfunction "2A0_36") (pintype "bidirectional"))
      (node (ref "U$1") (pin "8") (pinfunction "GPIOL_40_CDI8_8") (pintype "bidirectional"))
    )
    (net (code "20") (name "A8") (class "Default")
      (node (ref "IC8") (pin "37") (pinfunction "1A7_37") (pintype "bidirectional"))
      (node (ref "U$1") (pin "7") (pinfunction "GPIOL_41_CDI9_7") (pintype "bidirectional"))
    )
    (net (code "21") (name "A8_A0") (class "Default")
      (node (ref "DBG_CART") (pin "21") (pinfunction "21_21") (pintype "passive"))
      (node (ref "IC8") (pin "16") (pinfunction "2B2_16") (pintype "bidirectional"))
      (node (ref "U$2") (pin "5") (pinfunction "5:A0_5") (pintype "bidirectional"))
    )
    (net (code "22") (name "A8_A1") (class "Default")
      (node (ref "DBG_CART") (pin "23") (pinfunction "23_23") (pintype "passive"))
      (node (ref "IC8") (pin "19") (pinfunction "2B4_19") (pintype "bidirectional"))
      (node (ref "U$2") (pin "4") (pinfunction "4:A1_4") (pintype "bidirectional"))
    )
    (net (code "23") (name "A8_A2") (class "Default")
      (node (ref "DBG_CART") (pin "25") (pinfunction "25_25") (pintype "passive"))
      (node (ref "IC8") (pin "22") (pinfunction "2B6_22") (pintype "bidirectional"))
      (node (ref "U$2") (pin "3") (pinfunction "3:A2_3") (pintype "bidirectional"))
    )
    (net (code "24") (name "A8_A3") (class "Default")
      (node (ref "DBG_CART") (pin "27") (pinfunction "27_27") (pintype "passive"))
      (node (ref "IC8") (pin "23") (pinfunction "2B7_23") (pintype "bidirectional"))
      (node (ref "U$2") (pin "2") (pinfunction "2:A3_2") (pintype "bidirectional"))
    )
    (net (code "25") (name "A8_A4") (class "Default")
      (node (ref "DBG_CART") (pin "26") (pinfunction "26_26") (pintype "passive"))
      (node (ref "IC8") (pin "20") (pinfunction "2B5_20") (pintype "bidirectional"))
      (node (ref "U$2") (pin "C") (pinfunction "C:A4_C") (pintype "bidirectional"))
    )
    (net (code "26") (name "A8_A5") (class "Default")
      (node (ref "DBG_CART") (pin "24") (pinfunction "24_24") (pintype "passive"))
      (node (ref "IC8") (pin "17") (pinfunction "2B3_17") (pintype "bidirectional"))
      (node (ref "U$2") (pin "D") (pinfunction "D:A5_D") (pintype "bidirectional"))
    )
    (net (code "27") (name "A8_A6") (class "Default")
      (node (ref "DBG_CART") (pin "22") (pinfunction "22_22") (pintype "passive"))
      (node (ref "IC8") (pin "14") (pinfunction "2B1_14") (pintype "bidirectional"))
      (node (ref "U$2") (pin "E") (pinfunction "E:A6_E") (pintype "bidirectional"))
    )
    (net (code "28") (name "A8_A7") (class "Default")
      (node (ref "DBG_CART") (pin "20") (pinfunction "20_20") (pintype "passive"))
      (node (ref "IC8") (pin "13") (pinfunction "2B0_13") (pintype "bidirectional"))
      (node (ref "U$2") (pin "F") (pinfunction "F:A7_F") (pintype "bidirectional"))
    )
    (net (code "29") (name "A8_A8") (class "Default")
      (node (ref "DBG_CART") (pin "18") (pinfunction "18_18") (pintype "passive"))
      (node (ref "IC8") (pin "12") (pinfunction "1B7_12") (pintype "bidirectional"))
      (node (ref "U$2") (pin "H") (pinfunction "H:A8_H") (pintype "bidirectional"))
    )
    (net (code "30") (name "A8_A9") (class "Default")
      (node (ref "DBG_CART") (pin "16") (pinfunction "16_16") (pintype "passive"))
      (node (ref "IC8") (pin "11") (pinfunction "1B6_11") (pintype "bidirectional"))
      (node (ref "U$2") (pin "J") (pinfunction "J:A9_J") (pintype "bidirectional"))
    )
    (net (code "31") (name "A8_A10") (class "Default")
      (node (ref "DBG_CART") (pin "6") (pinfunction "6_6") (pintype "passive"))
      (node (ref "IC8") (pin "6") (pinfunction "1B3_6") (pintype "bidirectional"))
      (node (ref "U$2") (pin "P") (pinfunction "P:A10_P") (pintype "bidirectional"))
    )
    (net (code "32") (name "A8_A11") (class "Default")
      (node (ref "DBG_CART") (pin "8") (pinfunction "8_8") (pintype "passive"))
      (node (ref "IC8") (pin "8") (pinfunction "1B4_8") (pintype "bidirectional"))
      (node (ref "U$2") (pin "N") (pinfunction "N:A11_N") (pintype "bidirectional"))
    )
    (net (code "33") (name "A8_A12") (class "Default")
      (node (ref "DBG_CART") (pin "14") (pinfunction "14_14") (pintype "passive"))
      (node (ref "IC8") (pin "9") (pinfunction "1B5_9") (pintype "bidirectional"))
      (node (ref "U$2") (pin "K") (pinfunction "K:A12_K") (pintype "bidirectional"))
    )
    (net (code "34") (name "A8_A13") (class "Default")
      (node (ref "DBG_EXT") (pin "8") (pinfunction "8_8") (pintype "passive"))
      (node (ref "IC8") (pin "5") (pinfunction "1B2_5") (pintype "bidirectional"))
      (node (ref "U$2") (pin "E:D") (pinfunction "ED:A13_E:D") (pintype "bidirectional"))
    )
    (net (code "35") (name "A8_A14") (class "Default")
      (node (ref "DBG_EXT") (pin "6") (pinfunction "6_6") (pintype "passive"))
      (node (ref "IC8") (pin "3") (pinfunction "1B1_3") (pintype "bidirectional"))
      (node (ref "U$2") (pin "E:E") (pinfunction "EE:A14_E:E") (pintype "bidirectional"))
    )
    (net (code "36") (name "A8_A15") (class "Default")
      (node (ref "DBG_EXT") (pin "4") (pinfunction "4_4") (pintype "passive"))
      (node (ref "IC8") (pin "2") (pinfunction "1B0_2") (pintype "bidirectional"))
      (node (ref "U$2") (pin "E:F") (pinfunction "EF:A15_E:F") (pintype "bidirectional"))
    )
    (net (code "37") (name "A8_D0") (class "Default")
      (node (ref "DBG_CART") (pin "11") (pinfunction "11_11") (pintype "passive"))
      (node (ref "IC7") (pin "17") (pinfunction "2B3_17") (pintype "bidirectional"))
      (node (ref "U$2") (pin "10") (pinfunction "10:D0_10") (pintype "bidirectional"))
    )
    (net (code "38") (name "A8_D1") (class "Default")
      (node (ref "DBG_CART") (pin "13") (pinfunction "13_13") (pintype "passive"))
      (node (ref "IC7") (pin "19") (pinfunction "2B4_19") (pintype "bidirectional"))
      (node (ref "U$2") (pin "9") (pinfunction "9:D1_9") (pintype "bidirectional"))
    )
    (net (code "39") (name "A8_D2") (class "Default")
      (node (ref "DBG_CART") (pin "15") (pinfunction "15_15") (pintype "passive"))
      (node (ref "IC7") (pin "20") (pinfunction "2B5_20") (pintype "bidirectional"))
      (node (ref "U$2") (pin "8") (pinfunction "8:D2_8") (pintype "bidirectional"))
    )
    (net (code "40") (name "A8_D3") (class "Default")
      (node (ref "DBG_CART") (pin "12") (pinfunction "12_12") (pintype "passive"))
      (node (ref "IC7") (pin "16") (pinfunction "2B2_16") (pintype "bidirectional"))
      (node (ref "U$2") (pin "L") (pinfunction "L:D3_L") (pintype "bidirectional"))
    )
    (net (code "41") (name "A8_D4") (class "Default")
      (node (ref "DBG_CART") (pin "19") (pinfunction "19_19") (pintype "passive"))
      (node (ref "IC7") (pin "23") (pinfunction "2B7_23") (pintype "bidirectional"))
      (node (ref "U$2") (pin "6") (pinfunction "6:D4_6") (pintype "bidirectional"))
    )
    (net (code "42") (name "A8_D5") (class "Default")
      (node (ref "DBG_CART") (pin "17") (pinfunction "17_17") (pintype "passive"))
      (node (ref "IC7") (pin "22") (pinfunction "2B6_22") (pintype "bidirectional"))
      (node (ref "U$2") (pin "7") (pinfunction "7:D5_7") (pintype "bidirectional"))
    )
    (net (code "43") (name "A8_D6") (class "Default")
      (node (ref "DBG_CART") (pin "9") (pinfunction "9_9") (pintype "passive"))
      (node (ref "IC7") (pin "14") (pinfunction "2B1_14") (pintype "bidirectional"))
      (node (ref "U$2") (pin "11") (pinfunction "11:D6_11") (pintype "bidirectional"))
    )
    (net (code "44") (name "A8_D7") (class "Default")
      (node (ref "DBG_CART") (pin "10") (pinfunction "10_10") (pintype "passive"))
      (node (ref "IC7") (pin "13") (pinfunction "2B0_13") (pintype "bidirectional"))
      (node (ref "U$2") (pin "M") (pinfunction "M:D7_M") (pintype "bidirectional"))
    )
    (net (code "45") (name "A8_RD4") (class "Default")
      (node (ref "DBG_CART") (pin "30") (pinfunction "30_30") (pintype "passive"))
      (node (ref "IC7") (pin "11") (pinfunction "1B6_11") (pintype "bidirectional"))
      (node (ref "U$2") (pin "A") (pinfunction "A:RD4_A") (pintype "bidirectional"))
    )
    (net (code "46") (name "A8_RD5") (class "Default")
      (node (ref "DBG_CART") (pin "3") (pinfunction "3_3") (pintype "passive"))
      (node (ref "IC7") (pin "6") (pinfunction "1B3_6") (pintype "bidirectional"))
      (node (ref "U$2") (pin "14") (pinfunction "14:RD5_14") (pintype "bidirectional"))
    )
    (net (code "47") (name "A8_R{slash}~{W}") (class "Default")
      (node (ref "DBG_CART") (pin "4") (pinfunction "4_4") (pintype "passive"))
      (node (ref "IC4") (pin "4") (pinfunction "B_4") (pintype "bidirectional"))
      (node (ref "U$2") (pin "R") (pinfunction "R:R/~{W}_R") (pintype "bidirectional"))
    )
    (net (code "48") (name "A9") (class "Default")
      (node (ref "IC8") (pin "38") (pinfunction "1A6_38") (pintype "bidirectional"))
      (node (ref "U$1") (pin "6") (pinfunction "GPIOL_46_6") (pintype "bidirectional"))
    )
    (net (code "49") (name "A10") (class "Default")
      (node (ref "IC8") (pin "43") (pinfunction "1A3_43") (pintype "bidirectional"))
      (node (ref "U$1") (pin "144") (pinfunction "GPIOL_64_144") (pintype "bidirectional"))
    )
    (net (code "50") (name "A11") (class "Default")
      (node (ref "IC8") (pin "41") (pinfunction "1A4_41") (pintype "bidirectional"))
      (node (ref "U$1") (pin "3") (pinfunction "GPIOL_53_CDI10_3") (pintype "bidirectional"))
    )
    (net (code "51") (name "A12") (class "Default")
      (node (ref "IC8") (pin "40") (pinfunction "1A5_40") (pintype "bidirectional"))
      (node (ref "U$1") (pin "4") (pinfunction "GPIOL_54_CDI11_4") (pintype "bidirectional"))
    )
    (net (code "52") (name "A13") (class "Default")
      (node (ref "IC8") (pin "44") (pinfunction "1A2_44") (pintype "bidirectional"))
      (node (ref "U$1") (pin "142") (pinfunction "GPIOL_66_CDI12_142") (pintype "bidirectional"))
    )
    (net (code "53") (name "A14") (class "Default")
      (node (ref "IC8") (pin "46") (pinfunction "1A1_46") (pintype "bidirectional"))
      (node (ref "U$1") (pin "141") (pinfunction "GPIOL_65_141") (pintype "bidirectional"))
    )
    (net (code "54") (name "A15") (class "Default")
      (node (ref "IC8") (pin "47") (pinfunction "1A0_47") (pintype "bidirectional"))
      (node (ref "U$1") (pin "140") (pinfunction "GPIOL_67_CDI13_140") (pintype "bidirectional"))
    )
    (net (code "55") (name "AUDIO") (class "Default")
      (node (ref "DBG_EXT") (pin "5") (pinfunction "5_5") (pintype "passive"))
      (node (ref "U$2") (pin "E5") (pinfunction "E5:AUDIO_E5") (pintype "bidirectional"))
    )
    (net (code "56") (name "CBSEL0") (class "Default")
      (node (ref "R23") (pin "2") (pinfunction "2_2") (pintype "passive"))
      (node (ref "U$1") (pin "137") (pinfunction "GPIOL_70_CBSEL0_137") (pintype "bidirectional"))
    )
    (net (code "57") (name "CBSEL1") (class "Default")
      (node (ref "R24") (pin "2") (pinfunction "2_2") (pintype "passive"))
      (node (ref "U$1") (pin "138") (pinfunction "GPIOL_69_CBSEL1_138") (pintype "bidirectional"))
    )
    (net (code "58") (name "CBUS0") (class "Default")
      (node (ref "R6") (pin "2") (pinfunction "2_2") (pintype "passive"))
      (node (ref "U$1") (pin "78") (pinfunction "GPIOR_151_CBUS0_78") (pintype "bidirectional"))
    )
    (net (code "59") (name "CBUS1") (class "Default")
      (node (ref "R7") (pin "2") (pinfunction "2_2") (pintype "passive"))
      (node (ref "U$1") (pin "79") (pinfunction "GPIOR_150_CBUS1_79") (pintype "bidirectional"))
    )
    (net (code "60") (name "CBUS2") (class "Default")
      (node (ref "R8") (pin "2") (pinfunction "2_2") (pintype "passive"))
      (node (ref "U$1") (pin "80") (pinfunction "GPIOR_149_CBUS2_80") (pintype "bidirectional"))
    )
    (net (code "61") (name "CDONE") (class "Default")
      (node (ref "R3") (pin "2") (pinfunction "2_2") (pintype "passive"))
      (node (ref "R30") (pin "1") (pinfunction "1_1") (pintype "passive"))
      (node (ref "TTAG") (pin "3") (pinfunction "CDONE_3") (pintype "bidirectional"))
      (node (ref "U$1") (pin "34") (pinfunction "CDONE_34") (pintype "bidirectional"))
    )
    (net (code "62") (name "CLK") (class "Default")
      (node (ref "IC7") (pin "44") (pinfunction "1A2_44") (pintype "bidirectional"))
      (node (ref "U$1") (pin "110") (pinfunction "GPIOR_87_CDI29_110") (pintype "bidirectional"))
    )
    (net (code "63") (name "CLK25") (class "Default")
      (node (ref "U$1") (pin "75") (pinfunction "GPIOR_157_PLLIN_75") (pintype "bidirectional"))
      (node (ref "Y1") (pin "3") (pinfunction "OUT_3") (pintype "bidirectional"))
    )
    (net (code "64") (name "D0") (class "Default")
      (node (ref "IC7") (pin "32") (pinfunction "2A3_32") (pintype "bidirectional"))
      (node (ref "U$1") (pin "123") (pinfunction "GPIOR_77_PLLIN1_123") (pintype "bidirectional"))
    )
    (net (code "65") (name "D1") (class "Default")
      (node (ref "IC7") (pin "30") (pinfunction "2A4_30") (pintype "bidirectional"))
      (node (ref "U$1") (pin "124") (pinfunction "GPIOR_76_PLLIN0_124") (pintype "bidirectional"))
    )
    (net (code "66") (name "D2") (class "Default")
      (node (ref "IC7") (pin "29") (pinfunction "2A5_29") (pintype "bidirectional"))
      (node (ref "U$1") (pin "131") (pinfunction "GPIOL_75_PLLIN1_131") (pintype "bidirectional"))
    )
    (net (code "67") (name "D3") (class "Default")
      (node (ref "IC7") (pin "33") (pinfunction "2A2_33") (pintype "bidirectional"))
      (node (ref "U$1") (pin "119") (pinfunction "GPIOR_78_EXTFB0_CDI31_119") (pintype "bidirectional"))
    )
    (net (code "68") (name "D4") (class "Default")
      (node (ref "IC7") (pin "26") (pinfunction "2A7_26") (pintype "bidirectional"))
      (node (ref "U$1") (pin "134") (pinfunction "GPIOL_73_EXTFB1_CDI15_134") (pintype "bidirectional"))
    )
    (net (code "69") (name "D5") (class "Default")
      (node (ref "IC7") (pin "27") (pinfunction "2A6_27") (pintype "bidirectional"))
      (node (ref "U$1") (pin "132") (pinfunction "GPIOL_74_PLLIN0_132") (pintype "bidirectional"))
    )
    (net (code "70") (name "D6") (class "Default")
      (node (ref "IC7") (pin "35") (pinfunction "2A1_35") (pintype "bidirectional"))
      (node (ref "U$1") (pin "118") (pinfunction "GPIOR_79_EXTFB1_CDI30_118") (pintype "bidirectional"))
    )
    (net (code "71") (name "D7") (class "Default")
      (node (ref "IC7") (pin "36") (pinfunction "2A0_36") (pintype "bidirectional"))
      (node (ref "U$1") (pin "117") (pinfunction "GPIOR_80_117") (pintype "bidirectional"))
    )
    (net (code "72") (name "DIR_A") (class "Default")
      (node (ref "IC8") (pin "1") (pinfunction "1DIR_1") (pintype "bidirectional"))
      (node (ref "IC8") (pin "24") (pinfunction "2DIR_24") (pintype "bidirectional"))
      (node (ref "R10") (pin "2") (pinfunction "2_2") (pintype "passive"))
      (node (ref "U$1") (pin "139") (pinfunction "GPIOL_68_139") (pintype "bidirectional"))
    )
    (net (code "73") (name "DIR_D") (class "Default")
      (node (ref "IC7") (pin "24") (pinfunction "2DIR_24") (pintype "bidirectional"))
      (node (ref "R11") (pin "2") (pinfunction "2_2") (pintype "passive"))
      (node (ref "U$1") (pin "135") (pinfunction "GPIOL_72_EXTFB0_CDI14_135") (pintype "bidirectional"))
    )
    (net (code "74") (name "DIR_EXTSEL") (class "Default")
      (node (ref "IC10") (pin "5") (pinfunction "DIR_5") (pintype "bidirectional"))
      (node (ref "R17") (pin "1") (pinfunction "1_1") (pintype "passive"))
      (node (ref "U$1") (pin "106") (pinfunction "GPIOR_94_CDI27_106") (pintype "bidirectional"))
    )
    (net (code "75") (name "DIR_HALT") (class "Default")
      (node (ref "IC1") (pin "5") (pinfunction "DIR_5") (pintype "bidirectional"))
      (node (ref "R13") (pin "2") (pinfunction "2_2") (pintype "passive"))
      (node (ref "U$1") (pin "97") (pinfunction "GPIOR_122_CLK13_CDI21_97") (pintype "bidirectional"))
    )
    (net (code "76") (name "DIR_IN") (class "Default")
      (node (ref "IC7") (pin "1") (pinfunction "1DIR_1") (pintype "bidirectional"))
      (node (ref "R12") (pin "2") (pinfunction "2_2") (pintype "passive"))
      (node (ref "U$1") (pin "102") (pinfunction "GPIOR_105_CDI24_102") (pintype "bidirectional"))
    )
    (net (code "77") (name "DIR_IRQ") (class "Default")
      (node (ref "IC11") (pin "5") (pinfunction "DIR_5") (pintype "bidirectional"))
      (node (ref "R18") (pin "1") (pinfunction "1_1") (pintype "passive"))
      (node (ref "U$1") (pin "99") (pinfunction "GPIOR_116_CTRL15_99") (pintype "bidirectional"))
    )
    (net (code "78") (name "DIR_MPD") (class "Default")
      (node (ref "IC9") (pin "5") (pinfunction "DIR_5") (pintype "bidirectional"))
      (node (ref "R19") (pin "1") (pinfunction "1_1") (pintype "passive"))
      (node (ref "U$1") (pin "92") (pinfunction "GPIOR_125_CLK10_92") (pintype "bidirectional"))
    )
    (net (code "79") (name "DIR_REF") (class "Default")
      (node (ref "IC6") (pin "5") (pinfunction "DIR_5") (pintype "bidirectional"))
      (node (ref "R15") (pin "2") (pinfunction "2_2") (pintype "passive"))
      (node (ref "U$1") (pin "89") (pinfunction "GPIOR_129_CTRL10_89") (pintype "bidirectional"))
    )
    (net (code "80") (name "DIR_RST") (class "Default")
      (node (ref "IC5") (pin "5") (pinfunction "DIR_5") (pintype "bidirectional"))
      (node (ref "R14") (pin "2") (pinfunction "2_2") (pintype "passive"))
      (node (ref "U$1") (pin "101") (pinfunction "GPIOR_112_CDI23_101") (pintype "bidirectional"))
    )
    (net (code "81") (name "DIR_RW") (class "Default")
      (node (ref "IC4") (pin "5") (pinfunction "DIR_5") (pintype "bidirectional"))
      (node (ref "R16") (pin "2") (pinfunction "2_2") (pintype "passive"))
      (node (ref "U$1") (pin "113") (pinfunction "GPIOR_84_113") (pintype "bidirectional"))
    )
    (net (code "82") (name "GND") (class "Default")
      (node (ref "C1") (pin "2") (pinfunction "2_2") (pintype "passive"))
      (node (ref "C10") (pin "2") (pinfunction "2_2") (pintype "passive"))
      (node (ref "C11") (pin "2") (pinfunction "2_2") (pintype "passive"))
      (node (ref "C12") (pin "2") (pinfunction "2_2") (pintype "passive"))
      (node (ref "C13") (pin "2") (pinfunction "2_2") (pintype "passive"))
      (node (ref "C14") (pin "2") (pinfunction "2_2") (pintype "passive"))
      (node (ref "C15") (pin "2") (pinfunction "2_2") (pintype "passive"))
      (node (ref "C16") (pin "2") (pinfunction "2_2") (pintype "passive"))
      (node (ref "C17") (pin "2") (pinfunction "2_2") (pintype "passive"))
      (node (ref "C18") (pin "2") (pinfunction "2_2") (pintype "passive"))
      (node (ref "C19") (pin "2") (pinfunction "2_2") (pintype "passive"))
      (node (ref "C20") (pin "2") (pinfunction "2_2") (pintype "passive"))
      (node (ref "C21") (pin "2") (pinfunction "2_2") (pintype "passive"))
      (node (ref "C22") (pin "2") (pinfunction "2_2") (pintype "passive"))
      (node (ref "C23") (pin "2") (pinfunction "2_2") (pintype "passive"))
      (node (ref "C24") (pin "2") (pinfunction "2_2") (pintype "passive"))
      (node (ref "C25") (pin "2") (pinfunction "2_2") (pintype "passive"))
      (node (ref "C26") (pin "2") (pinfunction "2_2") (pintype "passive"))
      (node (ref "C27") (pin "2") (pinfunction "2_2") (pintype "passive"))
      (node (ref "C28") (pin "2") (pinfunction "2_2") (pintype "passive"))
      (node (ref "C29") (pin "2") (pinfunction "2_2") (pintype "passive"))
      (node (ref "C30") (pin "2") (pinfunction "2_2") (pintype "passive"))
      (node (ref "C31") (pin "2") (pinfunction "2_2") (pintype "passive"))
      (node (ref "C32") (pin "2") (pinfunction "2_2") (pintype "passive"))
      (node (ref "C33") (pin "2") (pinfunction "2_2") (pintype "passive"))
      (node (ref "C34") (pin "2") (pinfunction "2_2") (pintype "passive"))
      (node (ref "C35") (pin "2") (pinfunction "2_2") (pintype "passive"))
      (node (ref "C36") (pin "2") (pinfunction "2_2") (pintype "passive"))
      (node (ref "C37") (pin "2") (pinfunction "2_2") (pintype "passive"))
      (node (ref "C38") (pin "2") (pinfunction "2_2") (pintype "passive"))
      (node (ref "C39") (pin "2") (pinfunction "2_2") (pintype "passive"))
      (node (ref "C4") (pin "2") (pinfunction "2_2") (pintype "passive"))
      (node (ref "C40") (pin "2") (pinfunction "2_2") (pintype "passive"))
      (node (ref "C41") (pin "2") (pinfunction "2_2") (pintype "passive"))
      (node (ref "C42") (pin "2") (pinfunction "2_2") (pintype "passive"))
      (node (ref "C43") (pin "2") (pinfunction "2_2") (pintype "passive"))
      (node (ref "C44") (pin "2") (pinfunction "2_2") (pintype "passive"))
      (node (ref "C45") (pin "2") (pinfunction "2_2") (pintype "passive"))
      (node (ref "C46") (pin "2") (pinfunction "2_2") (pintype "passive"))
      (node (ref "C47") (pin "2") (pinfunction "2_2") (pintype "passive"))
      (node (ref "C48") (pin "2") (pinfunction "2_2") (pintype "passive"))
      (node (ref "C49") (pin "2") (pinfunction "2_2") (pintype "passive"))
      (node (ref "C5") (pin "2") (pinfunction "2_2") (pintype "passive"))
      (node (ref "C50") (pin "2") (pinfunction "2_2") (pintype "passive"))
      (node (ref "C51") (pin "2") (pinfunction "2_2") (pintype "passive"))
      (node (ref "C52") (pin "2") (pinfunction "2_2") (pintype "passive"))
      (node (ref "C53") (pin "2") (pinfunction "2_2") (pintype "passive"))
      (node (ref "C54") (pin "2") (pinfunction "2_2") (pintype "passive"))
      (node (ref "C55") (pin "2") (pinfunction "2_2") (pintype "passive"))
      (node (ref "C56") (pin "2") (pinfunction "2_2") (pintype "passive"))
      (node (ref "C6") (pin "2") (pinfunction "2_2") (pintype "passive"))
      (node (ref "C7") (pin "2") (pinfunction "2_2") (pintype "passive"))
      (node (ref "C8") (pin "2") (pinfunction "2_2") (pintype "passive"))
      (node (ref "C9") (pin "2") (pinfunction "2_2") (pintype "passive"))
      (node (ref "CBSEL0") (pin "3") (pinfunction "3_3") (pintype "passive"))
      (node (ref "CBSEL1") (pin "3") (pinfunction "3_3") (pintype "passive"))
      (node (ref "CBUS0") (pin "3") (pinfunction "3_3") (pintype "passive"))
      (node (ref "CBUS1") (pin "3") (pinfunction "3_3") (pintype "passive"))
      (node (ref "CBUS2") (pin "3") (pinfunction "3_3") (pintype "passive"))
      (node (ref "DBG_CART") (pin "28") (pinfunction "28_28") (pintype "passive"))
      (node (ref "DBG_EXT") (pin "2") (pinfunction "2_2") (pintype "passive"))
      (node (ref "DBG_XIO1") (pin "10") (pinfunction "10_10") (pintype "passive"))
      (node (ref "FLASH") (pin "4") (pinfunction "GND_4") (pintype "bidirectional"))
      (node (ref "H1") (pin "B3,0") (pinfunction "MOUNT_B3,0") (pintype "passive"))
      (node (ref "H2") (pin "B3,0") (pinfunction "MOUNT_B3,0") (pintype "passive"))
      (node (ref "IC1") (pin "2") (pinfunction "GND_2") (pintype "bidirectional"))
      (node (ref "IC10") (pin "2") (pinfunction "GND_2") (pintype "bidirectional"))
      (node (ref "IC11") (pin "2") (pinfunction "GND_2") (pintype "bidirectional"))
      (node (ref "IC12") (pin "2") (pinfunction "E_2") (pintype "bidirectional"))
      (node (ref "IC13") (pin "9") (pinfunction "GND_9") (pintype "bidirectional"))
      (node (ref "IC2") (pin "3") (pinfunction "GND_3") (pintype "bidirectional"))
      (node (ref "IC2") (pin "7") (pinfunction "GND_7") (pintype "bidirectional"))
      (node (ref "IC4") (pin "2") (pinfunction "GND_2") (pintype "bidirectional"))
      (node (ref "IC5") (pin "2") (pinfunction "GND_2") (pintype "bidirectional"))
      (node (ref "IC6") (pin "2") (pinfunction "GND_2") (pintype "bidirectional"))
      (node (ref "IC7") (pin "10") (pinfunction "GND_10") (pintype "bidirectional"))
      (node (ref "IC7") (pin "12") (pinfunction "1B7_12") (pintype "bidirectional"))
      (node (ref "IC7") (pin "15") (pinfunction "GND_15") (pintype "bidirectional"))
      (node (ref "IC7") (pin "21") (pinfunction "GND_21") (pintype "bidirectional"))
      (node (ref "IC7") (pin "25") (pinfunction "~{2OE}_25") (pintype "bidirectional"))
      (node (ref "IC7") (pin "28") (pinfunction "GND_28") (pintype "bidirectional"))
      (node (ref "IC7") (pin "34") (pinfunction "GND_34") (pintype "bidirectional"))
      (node (ref "IC7") (pin "37") (pinfunction "1A7_37") (pintype "bidirectional"))
      (node (ref "IC7") (pin "39") (pinfunction "GND_39") (pintype "bidirectional"))
      (node (ref "IC7") (pin "4") (pinfunction "GND_4") (pintype "bidirectional"))
      (node (ref "IC7") (pin "45") (pinfunction "GND_45") (pintype "bidirectional"))
      (node (ref "IC7") (pin "48") (pinfunction "~{1OE}_48") (pintype "bidirectional"))
      (node (ref "IC8") (pin "10") (pinfunction "GND_10") (pintype "bidirectional"))
      (node (ref "IC8") (pin "15") (pinfunction "GND_15") (pintype "bidirectional"))
      (node (ref "IC8") (pin "21") (pinfunction "GND_21") (pintype "bidirectional"))
      (node (ref "IC8") (pin "25") (pinfunction "~{2OE}_25") (pintype "bidirectional"))
      (node (ref "IC8") (pin "28") (pinfunction "GND_28") (pintype "bidirectional"))
      (node (ref "IC8") (pin "34") (pinfunction "GND_34") (pintype "bidirectional"))
      (node (ref "IC8") (pin "39") (pinfunction "GND_39") (pintype "bidirectional"))
      (node (ref "IC8") (pin "4") (pinfunction "GND_4") (pintype "bidirectional"))
      (node (ref "IC8") (pin "45") (pinfunction "GND_45") (pintype "bidirectional"))
      (node (ref "IC8") (pin "48") (pinfunction "~{1OE}_48") (pintype "bidirectional"))
      (node (ref "IC9") (pin "2") (pinfunction "GND_2") (pintype "bidirectional"))
      (node (ref "R10") (pin "1") (pinfunction "1_1") (pintype "passive"))
      (node (ref "R11") (pin "1") (pinfunction "1_1") (pintype "passive"))
      (node (ref "R12") (pin "1") (pinfunction "1_1") (pintype "passive"))
      (node (ref "R13") (pin "1") (pinfunction "1_1") (pintype "passive"))
      (node (ref "R14") (pin "1") (pinfunction "1_1") (pintype "passive"))
      (node (ref "R15") (pin "1") (pinfunction "1_1") (pintype "passive"))
      (node (ref "R16") (pin "1") (pinfunction "1_1") (pintype "passive"))
      (node (ref "R32") (pin "1") (pinfunction "1_1") (pintype "passive"))
      (node (ref "RESET") (pin "1") (pinfunction "1_1") (pintype "passive"))
      (node (ref "RESET") (pin "2") (pinfunction "2_2") (pintype "passive"))
      (node (ref "SPV") (pin "1") (pinfunction "GND_1") (pintype "bidirectional"))
      (node (ref "TTAG") (pin "2") (pinfunction "GND_2") (pintype "bidirectional"))
      (node (ref "TTAG") (pin "4") (pinfunction "GND_4") (pintype "bidirectional"))
      (node (ref "U$1") (pin "1") (pinfunction "GND_1") (pintype "bidirectional"))
      (node (ref "U$1") (pin "104") (pinfunction "GND_104") (pintype "bidirectional"))
      (node (ref "U$1") (pin "108") (pinfunction "GND_108") (pintype "bidirectional"))
      (node (ref "U$1") (pin "120") (pinfunction "GND_120") (pintype "bidirectional"))
      (node (ref "U$1") (pin "121") (pinfunction "GND_121") (pintype "bidirectional"))
      (node (ref "U$1") (pin "126") (pinfunction "GND_126") (pintype "bidirectional"))
      (node (ref "U$1") (pin "127") (pinfunction "GND_127") (pintype "bidirectional"))
      (node (ref "U$1") (pin "129") (pinfunction "GND_129") (pintype "bidirectional"))
      (node (ref "U$1") (pin "133") (pinfunction "GND_133") (pintype "bidirectional"))
      (node (ref "U$1") (pin "37") (pinfunction "GND_37") (pintype "bidirectional"))
      (node (ref "U$1") (pin "44") (pinfunction "GND_44") (pintype "bidirectional"))
      (node (ref "U$1") (pin "5") (pinfunction "GND_5") (pintype "bidirectional"))
      (node (ref "U$1") (pin "50") (pinfunction "GND_50") (pintype "bidirectional"))
      (node (ref "U$1") (pin "64") (pinfunction "GND_64") (pintype "bidirectional"))
      (node (ref "U$1") (pin "9") (pinfunction "GND_9") (pintype "bidirectional"))
      (node (ref "U$1") (pin "94") (pinfunction "GND_94") (pintype "bidirectional"))
      (node (ref "U$2") (pin "B") (pinfunction "B:GND_B") (pintype "bidirectional"))
      (node (ref "U$2") (pin "E:H") (pinfunction "EH:GND_E:H") (pintype "bidirectional"))
      (node (ref "Y1") (pin "2") (pinfunction "GND_2") (pintype "bidirectional"))
    )
    (net (code "83") (name "LED0") (class "Default")
      (node (ref "LD0") (pin "-") (pinfunction "-_-") (pintype "passive"))
      (node (ref "U$1") (pin "39") (pinfunction "GPIOB_TXN00_39") (pintype "bidirectional"))
    )
    (net (code "84") (name "LED1") (class "Default")
      (node (ref "LD1") (pin "-") (pinfunction "-_-") (pintype "passive"))
      (node (ref "U$1") (pin "41") (pinfunction "GPIOB_TXN02_41") (pintype "bidirectional"))
    )
    (net (code "85") (name "LED2") (class "Default")
      (node (ref "LD2") (pin "-") (pinfunction "-_-") (pintype "passive"))
      (node (ref "U$1") (pin "43") (pinfunction "GPIOB_TXN04_43") (pintype "bidirectional"))
    )
    (net (code "86") (name "Net-(CBSEL0-Pad2)") (class "Default")
      (node (ref "CBSEL0") (pin "2") (pinfunction "2_2") (pintype "passive"))
      (node (ref "R23") (pin "1") (pinfunction "1_1") (pintype "passive"))
    )
    (net (code "87") (name "Net-(CBSEL1-Pad2)") (class "Default")
      (node (ref "CBSEL1") (pin "2") (pinfunction "2_2") (pintype "passive"))
      (node (ref "R24") (pin "1") (pinfunction "1_1") (pintype "passive"))
    )
    (net (code "88") (name "Net-(CBUS0-Pad2)") (class "Default")
      (node (ref "CBUS0") (pin "2") (pinfunction "2_2") (pintype "passive"))
      (node (ref "R6") (pin "1") (pinfunction "1_1") (pintype "passive"))
    )
    (net (code "89") (name "Net-(CBUS1-Pad2)") (class "Default")
      (node (ref "CBUS1") (pin "2") (pinfunction "2_2") (pintype "passive"))
      (node (ref "R7") (pin "1") (pinfunction "1_1") (pintype "passive"))
    )
    (net (code "90") (name "Net-(CBUS2-Pad2)") (class "Default")
      (node (ref "CBUS2") (pin "2") (pinfunction "2_2") (pintype "passive"))
      (node (ref "R8") (pin "1") (pinfunction "1_1") (pintype "passive"))
    )
    (net (code "91") (name "Net-(DONE-Pad+)") (class "Default")
      (node (ref "DONE") (pin "+") (pinfunction "+_+") (pintype "passive"))
      (node (ref "R29") (pin "2") (pinfunction "2_2") (pintype "passive"))
    )
    (net (code "92") (name "Net-(IC2-OUT)") (class "Default")
      (node (ref "C1") (pin "1") (pinfunction "1_1") (pintype "passive"))
      (node (ref "IC2") (pin "5") (pinfunction "SNS_5") (pintype "bidirectional"))
      (node (ref "IC2") (pin "6") (pinfunction "OUT_6") (pintype "bidirectional"))
      (node (ref "V12") (pin "2") (pinfunction "2_2") (pintype "passive"))
    )
    (net (code "93") (name "Net-(IC12-B)") (class "Default")
      (node (ref "IC12") (pin "1") (pinfunction "B_1") (pintype "bidirectional"))
      (node (ref "R30") (pin "2") (pinfunction "2_2") (pintype "passive"))
    )
    (net (code "94") (name "Net-(IC12-C)") (class "Default")
      (node (ref "DONE") (pin "-") (pinfunction "-_-") (pintype "passive"))
      (node (ref "IC12") (pin "3") (pinfunction "C_3") (pintype "bidirectional"))
    )
    (net (code "95") (name "Net-(IC13-FB{slash}ADJ)") (class "Default")
      (node (ref "C56") (pin "1") (pinfunction "1_1") (pintype "passive"))
      (node (ref "IC13") (pin "1") (pinfunction "OUT_1") (pintype "bidirectional"))
      (node (ref "IC13") (pin "2") (pinfunction "OUT_2") (pintype "bidirectional"))
      (node (ref "IC13") (pin "4") (pinfunction "FB/ADJ_4") (pintype "bidirectional"))
      (node (ref "V3.3") (pin "2") (pinfunction "2_2") (pintype "passive"))
    )
    (net (code "96") (name "Net-(LD0-Pad+)") (class "Default")
      (node (ref "LD0") (pin "+") (pinfunction "+_+") (pintype "passive"))
      (node (ref "R33") (pin "2") (pinfunction "2_2") (pintype "passive"))
    )
    (net (code "97") (name "Net-(LD1-Pad+)") (class "Default")
      (node (ref "LD1") (pin "+") (pinfunction "+_+") (pintype "passive"))
      (node (ref "R34") (pin "2") (pinfunction "2_2") (pintype "passive"))
    )
    (net (code "98") (name "Net-(LD2-Pad+)") (class "Default")
      (node (ref "LD2") (pin "+") (pinfunction "+_+") (pintype "passive"))
      (node (ref "R35") (pin "2") (pinfunction "2_2") (pintype "passive"))
    )
    (net (code "99") (name "Net-(R31-Pad2)") (class "Default")
      (node (ref "R31") (pin "2") (pinfunction "2_2") (pintype "passive"))
      (node (ref "STATUS") (pin "+") (pinfunction "+_+") (pintype "passive"))
    )
    (net (code "100") (name "Net-(U$1A-REF_RES)") (class "Default")
      (node (ref "R32") (pin "2") (pinfunction "2_2") (pintype "passive"))
      (node (ref "U$1") (pin "36") (pinfunction "REF_RES_36") (pintype "bidirectional"))
    )
    (net (code "101") (name "PWRGD_1V2") (class "Default")
      (node (ref "IC13") (pin "6") (pinfunction "EN_6") (pintype "bidirectional"))
      (node (ref "IC2") (pin "4") (pinfunction "PG_4") (pintype "bidirectional"))
      (node (ref "R1") (pin "1") (pinfunction "1_1") (pintype "passive"))
    )
    (net (code "102") (name "RD4") (class "Default")
      (node (ref "IC7") (pin "38") (pinfunction "1A6_38") (pintype "bidirectional"))
      (node (ref "U$1") (pin "116") (pinfunction "GPIOR_81_MREFCLK_116") (pintype "bidirectional"))
    )
    (net (code "103") (name "RD5") (class "Default")
      (node (ref "IC7") (pin "43") (pinfunction "1A3_43") (pintype "bidirectional"))
      (node (ref "U$1") (pin "112") (pinfunction "GPIOR_86_112") (pintype "bidirectional"))
    )
    (net (code "104") (name "RSRVD") (class "Default")
      (node (ref "DBG_EXT") (pin "14") (pinfunction "14_14") (pintype "passive"))
      (node (ref "U$2") (pin "E:A") (pinfunction "EA:RSRVD_E:A") (pintype "bidirectional"))
    )
    (net (code "105") (name "R{slash}~{W}") (class "Default")
      (node (ref "IC4") (pin "3") (pinfunction "A_3") (pintype "bidirectional"))
      (node (ref "U$1") (pin "111") (pinfunction "GPIOR_85_111") (pintype "bidirectional"))
    )
    (net (code "106") (name "SPI_CLK") (class "Default")
      (node (ref "FLASH") (pin "6") (pinfunction "SCK_6") (pintype "bidirectional"))
      (node (ref "TTAG") (pin "13") (pinfunction "SCLK_13") (pintype "bidirectional"))
      (node (ref "U$1") (pin "30") (pinfunction "GPIOL_01_CCK_30") (pintype "bidirectional"))
    )
    (net (code "107") (name "SPI_CSI") (class "Default")
      (node (ref "R2") (pin "2") (pinfunction "2_2") (pintype "passive"))
      (node (ref "U$1") (pin "32") (pinfunction "GPIOL_04_CSI_32") (pintype "bidirectional"))
    )
    (net (code "108") (name "SPI_D0") (class "Default")
      (node (ref "FLASH") (pin "5") (pinfunction "MOSI_5") (pintype "bidirectional"))
      (node (ref "TTAG") (pin "11") (pinfunction "MOSI_11") (pintype "bidirectional"))
      (node (ref "U$1") (pin "29") (pinfunction "GPIOL_08_CDI0_29") (pintype "bidirectional"))
    )
    (net (code "109") (name "SPI_D1") (class "Default")
      (node (ref "FLASH") (pin "2") (pinfunction "MISO_2") (pintype "bidirectional"))
      (node (ref "TTAG") (pin "9") (pinfunction "MISO_9") (pintype "bidirectional"))
      (node (ref "U$1") (pin "28") (pinfunction "GPIOL_09_CDI1_28") (pintype "bidirectional"))
    )
    (net (code "110") (name "SPI_D2") (class "Default")
      (node (ref "FLASH") (pin "3") (pinfunction "WP_3") (pintype "bidirectional"))
      (node (ref "U$1") (pin "20") (pinfunction "GPIOL_12_CDI2_20") (pintype "bidirectional"))
    )
    (net (code "111") (name "SPI_D3") (class "Default")
      (node (ref "FLASH") (pin "7") (pinfunction "HOLD_7") (pintype "bidirectional"))
      (node (ref "TTAG") (pin "1") (pinfunction "HOLD_1") (pintype "bidirectional"))
      (node (ref "U$1") (pin "19") (pinfunction "GPIOL_13_CDI3_19") (pintype "bidirectional"))
    )
    (net (code "112") (name "SPI_SS") (class "Default")
      (node (ref "FLASH") (pin "1") (pinfunction "CS_1") (pintype "bidirectional"))
      (node (ref "R4") (pin "2") (pinfunction "2_2") (pintype "passive"))
      (node (ref "TTAG") (pin "7") (pinfunction "~{CS}_7") (pintype "bidirectional"))
      (node (ref "U$1") (pin "31") (pinfunction "GPIOL_00_SS_N_31") (pintype "bidirectional"))
    )
    (net (code "113") (name "TCK") (class "Default")
      (node (ref "R28") (pin "2") (pinfunction "2_2") (pintype "passive"))
      (node (ref "TTAG") (pin "8") (pinfunction "TCK_8") (pintype "bidirectional"))
      (node (ref "U$1") (pin "26") (pinfunction "TCK_26") (pintype "bidirectional"))
    )
    (net (code "114") (name "TDI") (class "Default")
      (node (ref "R26") (pin "2") (pinfunction "2_2") (pintype "passive"))
      (node (ref "TTAG") (pin "14") (pinfunction "TDI_14") (pintype "bidirectional"))
      (node (ref "U$1") (pin "27") (pinfunction "TDI_27") (pintype "bidirectional"))
    )
    (net (code "115") (name "TDO") (class "Default")
      (node (ref "R27") (pin "2") (pinfunction "2_2") (pintype "passive"))
      (node (ref "TTAG") (pin "12") (pinfunction "TDO_12") (pintype "bidirectional"))
      (node (ref "U$1") (pin "24") (pinfunction "TDO_24") (pintype "bidirectional"))
    )
    (net (code "116") (name "TMS") (class "Default")
      (node (ref "R25") (pin "2") (pinfunction "2_2") (pintype "passive"))
      (node (ref "TTAG") (pin "10") (pinfunction "TMS_10") (pintype "bidirectional"))
      (node (ref "U$1") (pin "25") (pinfunction "TMS_25") (pintype "bidirectional"))
    )
    (net (code "117") (name "XIO_BOX_CLK") (class "Default")
      (node (ref "DBG_XIO0") (pin "9") (pinfunction "9_9") (pintype "passive"))
      (node (ref "U$1") (pin "69") (pinfunction "GPIOB_RXN12_EXTFB0_69") (pintype "bidirectional"))
      (node (ref "UHDMI") (pin "19") (pinfunction "BOX_CLK_19") (pintype "bidirectional"))
    )
    (net (code "118") (name "XIO_BOX_CTS") (class "Default")
      (node (ref "DBG_XIO1") (pin "9") (pinfunction "9_9") (pintype "passive"))
      (node (ref "U$1") (pin "55") (pinfunction "GPIOB_RXP00_55") (pintype "bidirectional"))
      (node (ref "UHDMI") (pin "18") (pinfunction "BOX_CTS_18") (pintype "bidirectional"))
    )
    (net (code "119") (name "XIO_BOX_RTS") (class "Default")
      (node (ref "DBG_XIO1") (pin "1") (pinfunction "1_1") (pintype "passive"))
      (node (ref "U$1") (pin "68") (pinfunction "GPIOB_RXN10_68") (pintype "bidirectional"))
      (node (ref "UHDMI") (pin "17") (pinfunction "BOX_RTS_17") (pintype "bidirectional"))
    )
    (net (code "120") (name "XIO_D0") (class "Default")
      (node (ref "DBG_XIO0") (pin "1") (pinfunction "1_1") (pintype "passive"))
      (node (ref "U$1") (pin "84") (pinfunction "GPIOR_135_CDI17_84") (pintype "bidirectional"))
      (node (ref "UHDMI") (pin "3") (pinfunction "D0_3") (pintype "bidirectional"))
    )
    (net (code "121") (name "XIO_D1") (class "Default")
      (node (ref "DBG_XIO0") (pin "7") (pinfunction "7_7") (pintype "passive"))
      (node (ref "U$1") (pin "72") (pinfunction "GPIOB_CLKN0_72") (pintype "bidirectional"))
      (node (ref "UHDMI") (pin "5") (pinfunction "D1_5") (pintype "bidirectional"))
    )
    (net (code "122") (name "XIO_D2") (class "Default")
      (node (ref "DBG_XIO0") (pin "6") (pinfunction "6_6") (pintype "passive"))
      (node (ref "U$1") (pin "81") (pinfunction "GPIOR_139_81") (pintype "bidirectional"))
      (node (ref "UHDMI") (pin "6") (pinfunction "D2_6") (pintype "bidirectional"))
    )
    (net (code "123") (name "XIO_D3") (class "Default")
      (node (ref "DBG_XIO0") (pin "5") (pinfunction "5_5") (pintype "passive"))
      (node (ref "U$1") (pin "77") (pinfunction "GPIOR_154_77") (pintype "bidirectional"))
      (node (ref "UHDMI") (pin "8") (pinfunction "D3_8") (pintype "bidirectional"))
    )
    (net (code "124") (name "XIO_D4") (class "Default")
      (node (ref "DBG_XIO1") (pin "8") (pinfunction "8_8") (pintype "passive"))
      (node (ref "U$1") (pin "56") (pinfunction "GPIOB_RXN00_56") (pintype "bidirectional"))
      (node (ref "UHDMI") (pin "9") (pinfunction "D4_9") (pintype "bidirectional"))
    )
    (net (code "125") (name "XIO_D5") (class "Default")
      (node (ref "DBG_XIO1") (pin "6") (pinfunction "6_6") (pintype "passive"))
      (node (ref "U$1") (pin "59") (pinfunction "GPIOB_RXN02_59") (pintype "bidirectional"))
      (node (ref "UHDMI") (pin "11") (pinfunction "D5_11") (pintype "bidirectional"))
    )
    (net (code "126") (name "XIO_D6") (class "Default")
      (node (ref "DBG_XIO1") (pin "2") (pinfunction "2_2") (pintype "passive"))
      (node (ref "U$1") (pin "66") (pinfunction "GPIOB_RXP07_66") (pintype "bidirectional"))
      (node (ref "UHDMI") (pin "12") (pinfunction "D6_12") (pintype "bidirectional"))
    )
    (net (code "127") (name "XIO_D7") (class "Default")
      (node (ref "DBG_XIO1") (pin "4") (pinfunction "4_4") (pintype "passive"))
      (node (ref "U$1") (pin "61") (pinfunction "GPIOB_RXP03_61") (pintype "bidirectional"))
      (node (ref "UHDMI") (pin "14") (pinfunction "D7_14") (pintype "bidirectional"))
    )
    (net (code "128") (name "XIO_HOST_CLK") (class "Default")
      (node (ref "DBG_XIO1") (pin "3") (pinfunction "3_3") (pintype "passive"))
      (node (ref "U$1") (pin "65") (pinfunction "GPIOB_RXN07_65") (pintype "bidirectional"))
      (node (ref "UHDMI") (pin "15") (pinfunction "HOST_CLK_15") (pintype "bidirectional"))
    )
    (net (code "129") (name "XIO_HOST_CTS") (class "Default")
      (node (ref "DBG_XIO0") (pin "4") (pinfunction "4_4") (pintype "passive"))
      (node (ref "U$1") (pin "83") (pinfunction "GPIOR_136_CDI16_83") (pintype "bidirectional"))
      (node (ref "UHDMI") (pin "2") (pinfunction "HOST_CTS_2") (pintype "bidirectional"))
    )
    (net (code "130") (name "XIO_HOST_RTS") (class "Default")
      (node (ref "DBG_XIO0") (pin "2") (pinfunction "2_2") (pintype "passive"))
      (node (ref "U$1") (pin "86") (pinfunction "GPIOR_133_CDI18_86") (pintype "bidirectional"))
      (node (ref "UHDMI") (pin "1") (pinfunction "HOST_RTS_1") (pintype "bidirectional"))
    )
    (net (code "131") (name "XIO_SHLD1") (class "Default")
      (node (ref "DBG_XIO0") (pin "3") (pinfunction "3_3") (pintype "passive"))
      (node (ref "U$1") (pin "82") (pinfunction "GPIOR_138_82") (pintype "bidirectional"))
      (node (ref "UHDMI") (pin "4") (pinfunction "SHLD1_4") (pintype "bidirectional"))
    )
    (net (code "132") (name "XIO_SHLD2") (class "Default")
      (node (ref "DBG_XIO0") (pin "10") (pinfunction "10_10") (pintype "passive"))
      (node (ref "U$1") (pin "71") (pinfunction "GPIOB_CLKP0_71") (pintype "bidirectional"))
      (node (ref "UHDMI") (pin "7") (pinfunction "SHLD2_7") (pintype "bidirectional"))
    )
    (net (code "133") (name "XIO_SHLD3") (class "Default")
      (node (ref "DBG_XIO0") (pin "8") (pinfunction "8_8") (pintype "passive"))
      (node (ref "U$1") (pin "76") (pinfunction "GPIOR_155_76") (pintype "bidirectional"))
      (node (ref "UHDMI") (pin "10") (pinfunction "SHLF3_10") (pintype "bidirectional"))
    )
    (net (code "134") (name "XIO_SHLD4") (class "Default")
      (node (ref "DBG_XIO1") (pin "5") (pinfunction "5_5") (pintype "passive"))
      (node (ref "U$1") (pin "60") (pinfunction "GPIOB_RXN03_60") (pintype "bidirectional"))
      (node (ref "UHDMI") (pin "13") (pinfunction "SHLD4_13") (pintype "bidirectional"))
    )
    (net (code "135") (name "XIO_SHLD5") (class "Default")
      (node (ref "DBG_XIO1") (pin "7") (pinfunction "7_7") (pintype "passive"))
      (node (ref "U$1") (pin "58") (pinfunction "GPIOB_RXP02_58") (pintype "bidirectional"))
      (node (ref "UHDMI") (pin "16") (pinfunction "SHLD5_16") (pintype "bidirectional"))
    )
    (net (code "136") (name "unconnected-(IC13-GND-Pad5)") (class "Default")
      (node (ref "IC13") (pin "5") (pinfunction "GND_5") (pintype "bidirectional"))
    )
    (net (code "137") (name "unconnected-(IC13-N{slash}C-Pad3)") (class "Default")
      (node (ref "IC13") (pin "3") (pinfunction "N/C_3") (pintype "no_connect"))
    )
    (net (code "138") (name "unconnected-(U$1A-GPIOB_RXP10-Pad67)") (class "Default")
      (node (ref "U$1") (pin "67") (pinfunction "GPIOB_RXP10_67") (pintype "bidirectional"))
    )
    (net (code "139") (name "unconnected-(U$1A-GPIOB_RXP12_EXTFB0-Pad70)") (class "Default")
      (node (ref "U$1") (pin "70") (pinfunction "GPIOB_RXP12_EXTFB0_70") (pintype "bidirectional"))
    )
    (net (code "140") (name "unconnected-(U$1A-GPIOB_TXN06-Pad46)") (class "Default")
      (node (ref "U$1") (pin "46") (pinfunction "GPIOB_TXN06_46") (pintype "bidirectional"))
    )
    (net (code "141") (name "unconnected-(U$1A-GPIOB_TXN09-Pad48)") (class "Default")
      (node (ref "U$1") (pin "48") (pinfunction "GPIOB_TXN09_48") (pintype "bidirectional"))
    )
    (net (code "142") (name "unconnected-(U$1A-GPIOB_TXN11-Pad54)") (class "Default")
      (node (ref "U$1") (pin "54") (pinfunction "GPIOB_TXN11_54") (pintype "bidirectional"))
    )
    (net (code "143") (name "unconnected-(U$1A-GPIOB_TXP00-Pad38)") (class "Default")
      (node (ref "U$1") (pin "38") (pinfunction "GPIOB_TXP00_38") (pintype "bidirectional"))
    )
    (net (code "144") (name "unconnected-(U$1A-GPIOB_TXP02-Pad40)") (class "Default")
      (node (ref "U$1") (pin "40") (pinfunction "GPIOB_TXP02_40") (pintype "bidirectional"))
    )
    (net (code "145") (name "unconnected-(U$1A-GPIOB_TXP04-Pad42)") (class "Default")
      (node (ref "U$1") (pin "42") (pinfunction "GPIOB_TXP04_42") (pintype "bidirectional"))
    )
    (net (code "146") (name "unconnected-(U$1A-GPIOB_TXP06-Pad45)") (class "Default")
      (node (ref "U$1") (pin "45") (pinfunction "GPIOB_TXP06_45") (pintype "bidirectional"))
    )
    (net (code "147") (name "unconnected-(U$1A-GPIOB_TXP09-Pad47)") (class "Default")
      (node (ref "U$1") (pin "47") (pinfunction "GPIOB_TXP09_47") (pintype "bidirectional"))
    )
    (net (code "148") (name "unconnected-(U$1A-GPIOB_TXP11-Pad53)") (class "Default")
      (node (ref "U$1") (pin "53") (pinfunction "GPIOB_TXP11_53") (pintype "bidirectional"))
    )
    (net (code "149") (name "unconnected-(U$1B-GPIOL_05_CS0-Pad33)") (class "Default")
      (node (ref "U$1") (pin "33") (pinfunction "GPIOL_05_CS0_33") (pintype "bidirectional"))
    )
    (net (code "150") (name "unconnected-(UHDMI-GND-PadMH1)") (class "Default")
      (node (ref "UHDMI") (pin "MH1") (pinfunction "GND_MH1") (pintype "bidirectional"))
    )
    (net (code "151") (name "unconnected-(UHDMI-GND-PadMH2)") (class "Default")
      (node (ref "UHDMI") (pin "MH2") (pinfunction "GND_MH2") (pintype "bidirectional"))
    )
    (net (code "152") (name "unconnected-(UHDMI-GND-PadMP1)") (class "Default")
      (node (ref "UHDMI") (pin "MP1") (pinfunction "GND_MP1") (pintype "bidirectional"))
    )
    (net (code "153") (name "unconnected-(UHDMI-GND-PadMP2)") (class "Default")
      (node (ref "UHDMI") (pin "MP2") (pinfunction "GND_MP2") (pintype "bidirectional"))
    )
    (net (code "154") (name "~{A8_CCTL}") (class "Default")
      (node (ref "DBG_CART") (pin "1") (pinfunction "1_1") (pintype "passive"))
      (node (ref "IC7") (pin "3") (pinfunction "1B1_3") (pintype "bidirectional"))
      (node (ref "U$2") (pin "15") (pinfunction "15:CCTL_15") (pintype "bidirectional"))
    )
    (net (code "155") (name "~{A8_CLK}") (class "Default")
      (node (ref "DBG_CART") (pin "2") (pinfunction "2_2") (pintype "passive"))
      (node (ref "IC7") (pin "5") (pinfunction "1B2_5") (pintype "bidirectional"))
      (node (ref "U$2") (pin "S") (pinfunction "S:CLK_S") (pintype "bidirectional"))
    )
    (net (code "156") (name "~{A8_D1XX}") (class "Default")
      (node (ref "DBG_EXT") (pin "9") (pinfunction "9_9") (pintype "passive"))
      (node (ref "IC7") (pin "2") (pinfunction "1B0_2") (pintype "bidirectional"))
      (node (ref "U$2") (pin "E3") (pinfunction "E3:~{D1XX}_E3") (pintype "bidirectional"))
    )
    (net (code "157") (name "~{A8_EXTSEL}") (class "Default")
      (node (ref "DBG_EXT") (pin "13") (pinfunction "13_13") (pintype "passive"))
      (node (ref "IC10") (pin "4") (pinfunction "B_4") (pintype "bidirectional"))
      (node (ref "U$2") (pin "E1") (pinfunction "E1:~{EXTSEL}_E1") (pintype "bidirectional"))
    )
    (net (code "158") (name "~{A8_HALT}") (class "Default")
      (node (ref "DBG_EXT") (pin "10") (pinfunction "10_10") (pintype "passive"))
      (node (ref "IC1") (pin "4") (pinfunction "B_4") (pintype "bidirectional"))
      (node (ref "U$2") (pin "E:C") (pinfunction "EC:~{HALT}_E:C") (pintype "bidirectional"))
    )
    (net (code "159") (name "~{A8_IRQ}") (class "Default")
      (node (ref "DBG_EXT") (pin "12") (pinfunction "12_12") (pintype "passive"))
      (node (ref "IC11") (pin "4") (pinfunction "B_4") (pintype "bidirectional"))
      (node (ref "U$2") (pin "E:B") (pinfunction "EB:~{IRQ}_E:B") (pintype "bidirectional"))
    )
    (net (code "160") (name "~{A8_MPD}") (class "Default")
      (node (ref "DBG_EXT") (pin "7") (pinfunction "7_7") (pintype "passive"))
      (node (ref "IC9") (pin "4") (pinfunction "B_4") (pintype "bidirectional"))
      (node (ref "U$2") (pin "E4") (pinfunction "E4:~{MPD}_E4") (pintype "bidirectional"))
    )
    (net (code "161") (name "~{A8_REF}") (class "Default")
      (node (ref "DBG_EXT") (pin "3") (pinfunction "3_3") (pintype "passive"))
      (node (ref "IC6") (pin "4") (pinfunction "B_4") (pintype "bidirectional"))
      (node (ref "U$2") (pin "E6") (pinfunction "E6:~{REF}_E6") (pintype "bidirectional"))
    )
    (net (code "162") (name "~{A8_RESET}") (class "Default")
      (node (ref "DBG_EXT") (pin "11") (pinfunction "11_11") (pintype "passive"))
      (node (ref "IC5") (pin "4") (pinfunction "B_4") (pintype "bidirectional"))
      (node (ref "U$2") (pin "E2") (pinfunction "E2:~{RESET}_E2") (pintype "bidirectional"))
    )
    (net (code "163") (name "~{A8_S4}") (class "Default")
      (node (ref "DBG_CART") (pin "29") (pinfunction "29_29") (pintype "passive"))
      (node (ref "IC7") (pin "9") (pinfunction "1B5_9") (pintype "bidirectional"))
      (node (ref "U$2") (pin "1") (pinfunction "1:S4_1") (pintype "bidirectional"))
    )
    (net (code "164") (name "~{A8_S5}") (class "Default")
      (node (ref "DBG_CART") (pin "7") (pinfunction "7_7") (pintype "passive"))
      (node (ref "IC7") (pin "8") (pinfunction "1B4_8") (pintype "bidirectional"))
      (node (ref "U$2") (pin "12") (pinfunction "12:S5_12") (pintype "bidirectional"))
    )
    (net (code "165") (name "~{CCTL}") (class "Default")
      (node (ref "IC7") (pin "46") (pinfunction "1A1_46") (pintype "bidirectional"))
      (node (ref "U$1") (pin "109") (pinfunction "GPIOR_88_CDI28_109") (pintype "bidirectional"))
    )
    (net (code "166") (name "~{CRESET}") (class "Default")
      (node (ref "C52") (pin "1") (pinfunction "1_1") (pintype "passive"))
      (node (ref "R9") (pin "2") (pinfunction "2_2") (pintype "passive"))
      (node (ref "RESET") (pin "3") (pinfunction "3_3") (pintype "passive"))
      (node (ref "RESET") (pin "4") (pinfunction "4_4") (pintype "passive"))
      (node (ref "SPV") (pin "2") (pinfunction "~{RESET}_2") (pintype "bidirectional"))
      (node (ref "TTAG") (pin "5") (pinfunction "CRESET_5") (pintype "bidirectional"))
      (node (ref "U$1") (pin "35") (pinfunction "~{CRESET}_35") (pintype "bidirectional"))
    )
    (net (code "167") (name "~{D1XX}") (class "Default")
      (node (ref "IC7") (pin "47") (pinfunction "1A0_47") (pintype "bidirectional"))
      (node (ref "U$1") (pin "103") (pinfunction "GPIOR_104_CDI25_103") (pintype "bidirectional"))
    )
    (net (code "168") (name "~{EXTSEL}") (class "Default")
      (node (ref "IC10") (pin "3") (pinfunction "A_3") (pintype "bidirectional"))
      (node (ref "R22") (pin "1") (pinfunction "1_1") (pintype "passive"))
      (node (ref "U$1") (pin "100") (pinfunction "GPIOR_113_CDI22_100") (pintype "bidirectional"))
    )
    (net (code "169") (name "~{HALT}") (class "Default")
      (node (ref "IC1") (pin "3") (pinfunction "A_3") (pintype "bidirectional"))
      (node (ref "U$1") (pin "93") (pinfunction "GPIOR_123_CLK12_CDI20_93") (pintype "bidirectional"))
    )
    (net (code "170") (name "~{IRQ}") (class "Default")
      (node (ref "IC11") (pin "3") (pinfunction "A_3") (pintype "bidirectional"))
      (node (ref "R21") (pin "1") (pinfunction "1_1") (pintype "passive"))
      (node (ref "U$1") (pin "105") (pinfunction "GPIOR_95_CDI26_105") (pintype "bidirectional"))
    )
    (net (code "171") (name "~{MPD}") (class "Default")
      (node (ref "IC9") (pin "3") (pinfunction "A_3") (pintype "bidirectional"))
      (node (ref "R20") (pin "1") (pinfunction "1_1") (pintype "passive"))
      (node (ref "U$1") (pin "90") (pinfunction "GPIOR_128_CTRL11_90") (pintype "bidirectional"))
    )
    (net (code "172") (name "~{REF}") (class "Default")
      (node (ref "IC6") (pin "3") (pinfunction "A_3") (pintype "bidirectional"))
      (node (ref "U$1") (pin "87") (pinfunction "GPIOR_132_CDI19_87") (pintype "bidirectional"))
    )
    (net (code "173") (name "~{RESET}") (class "Default")
      (node (ref "IC5") (pin "3") (pinfunction "A_3") (pintype "bidirectional"))
      (node (ref "U$1") (pin "98") (pinfunction "GPIOR_117_CTRL14_98") (pintype "bidirectional"))
    )
    (net (code "174") (name "~{S4}") (class "Default")
      (node (ref "IC7") (pin "40") (pinfunction "1A5_40") (pintype "bidirectional"))
      (node (ref "U$1") (pin "115") (pinfunction "GPIOR_82_115") (pintype "bidirectional"))
    )
    (net (code "175") (name "~{S5}") (class "Default")
      (node (ref "IC7") (pin "41") (pinfunction "1A4_41") (pintype "bidirectional"))
      (node (ref "U$1") (pin "114") (pinfunction "GPIOR_83_114") (pintype "bidirectional"))
    )
    (net (code "176") (name "~{STATUS}") (class "Default")
      (node (ref "STATUS") (pin "-") (pinfunction "-_-") (pintype "passive"))
      (node (ref "TTAG") (pin "6") (pinfunction "~{STATUS}_6") (pintype "bidirectional"))
      (node (ref "U$1") (pin "136") (pinfunction "GPIOL_71_~{STATUS}_136") (pintype "bidirectional"))
    )
    (net (code "177") (name "~{TEST}") (class "Default")
      (node (ref "R5") (pin "2") (pinfunction "2_2") (pintype "passive"))
      (node (ref "U$1") (pin "74") (pinfunction "GPIOR_158_~{TEST}_74") (pintype "bidirectional"))
    )
  )
)
